# haasoscope_pro_fpga_board_-_power_and_fa.net
KiCad netlist of a schematic drawn in EAGLE
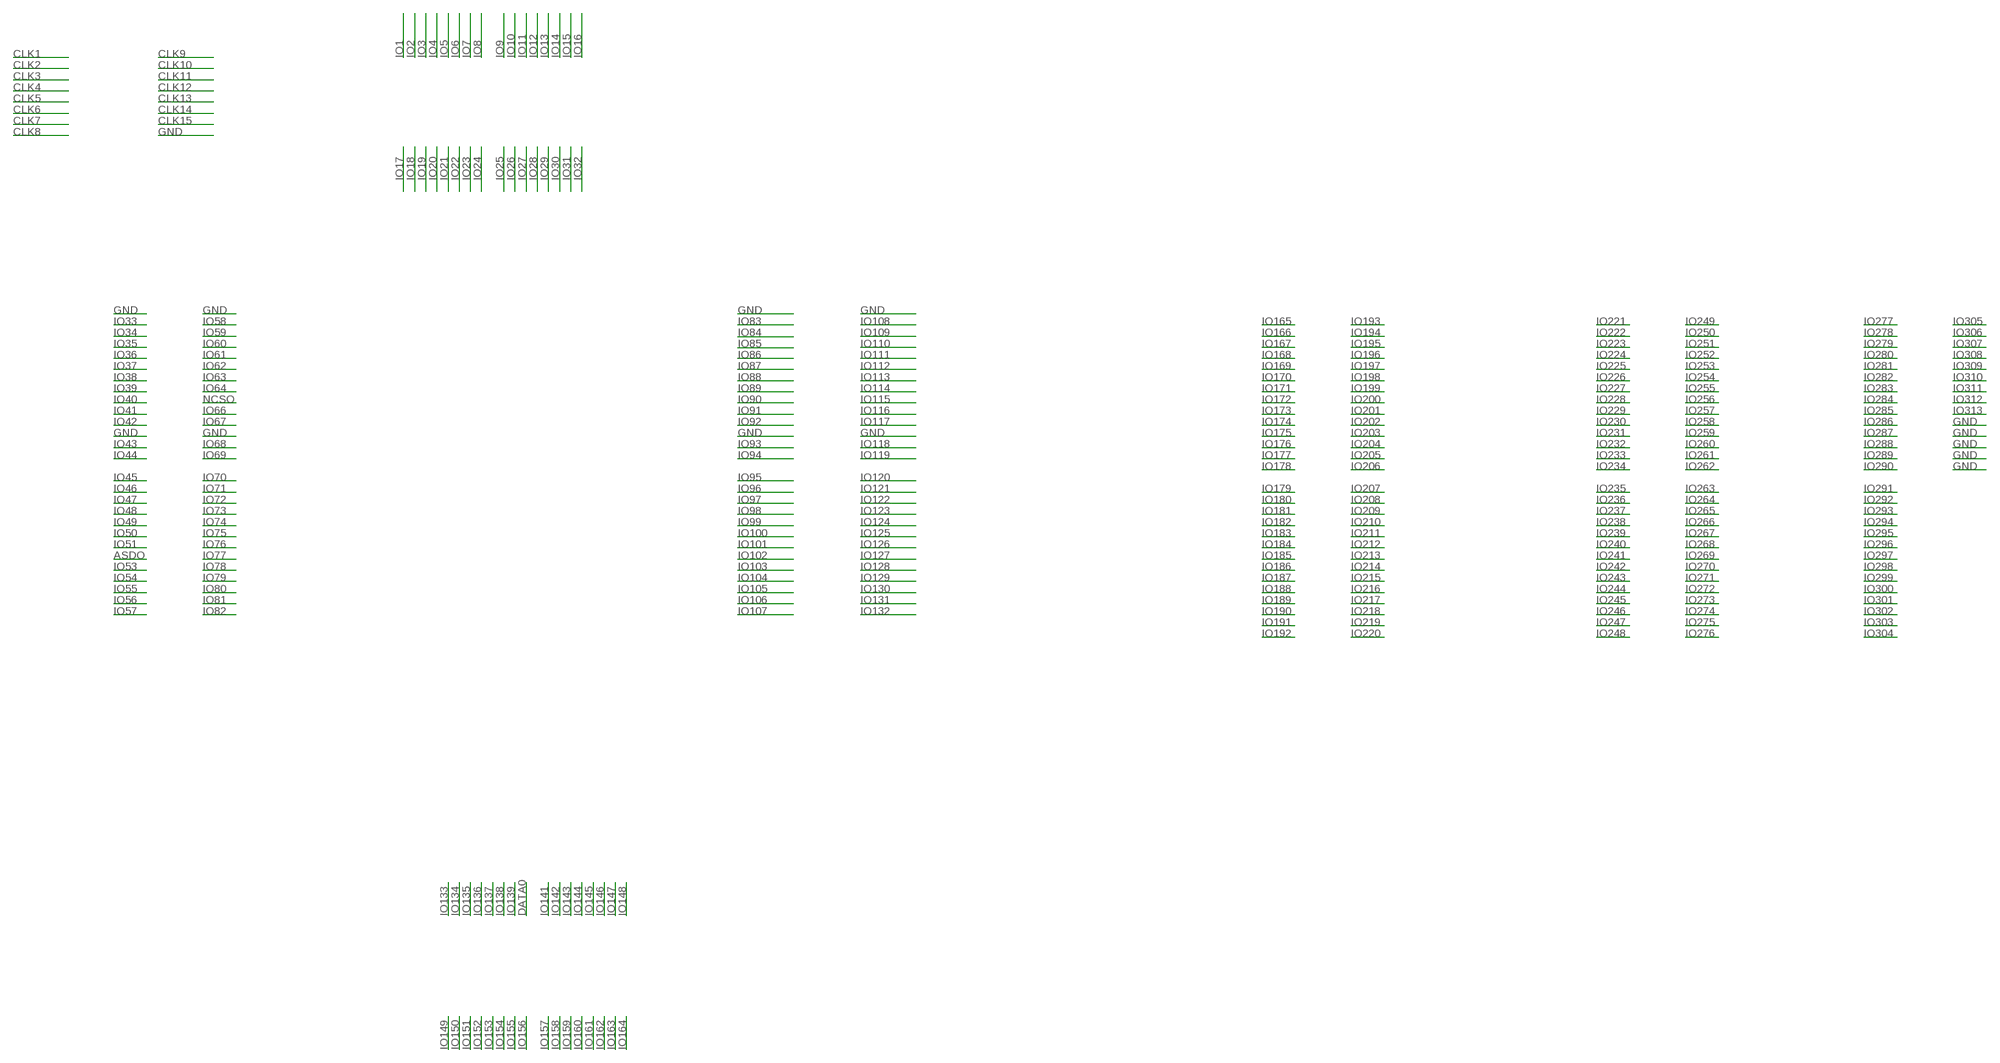
[diagram p0: schematic, sheet 1]
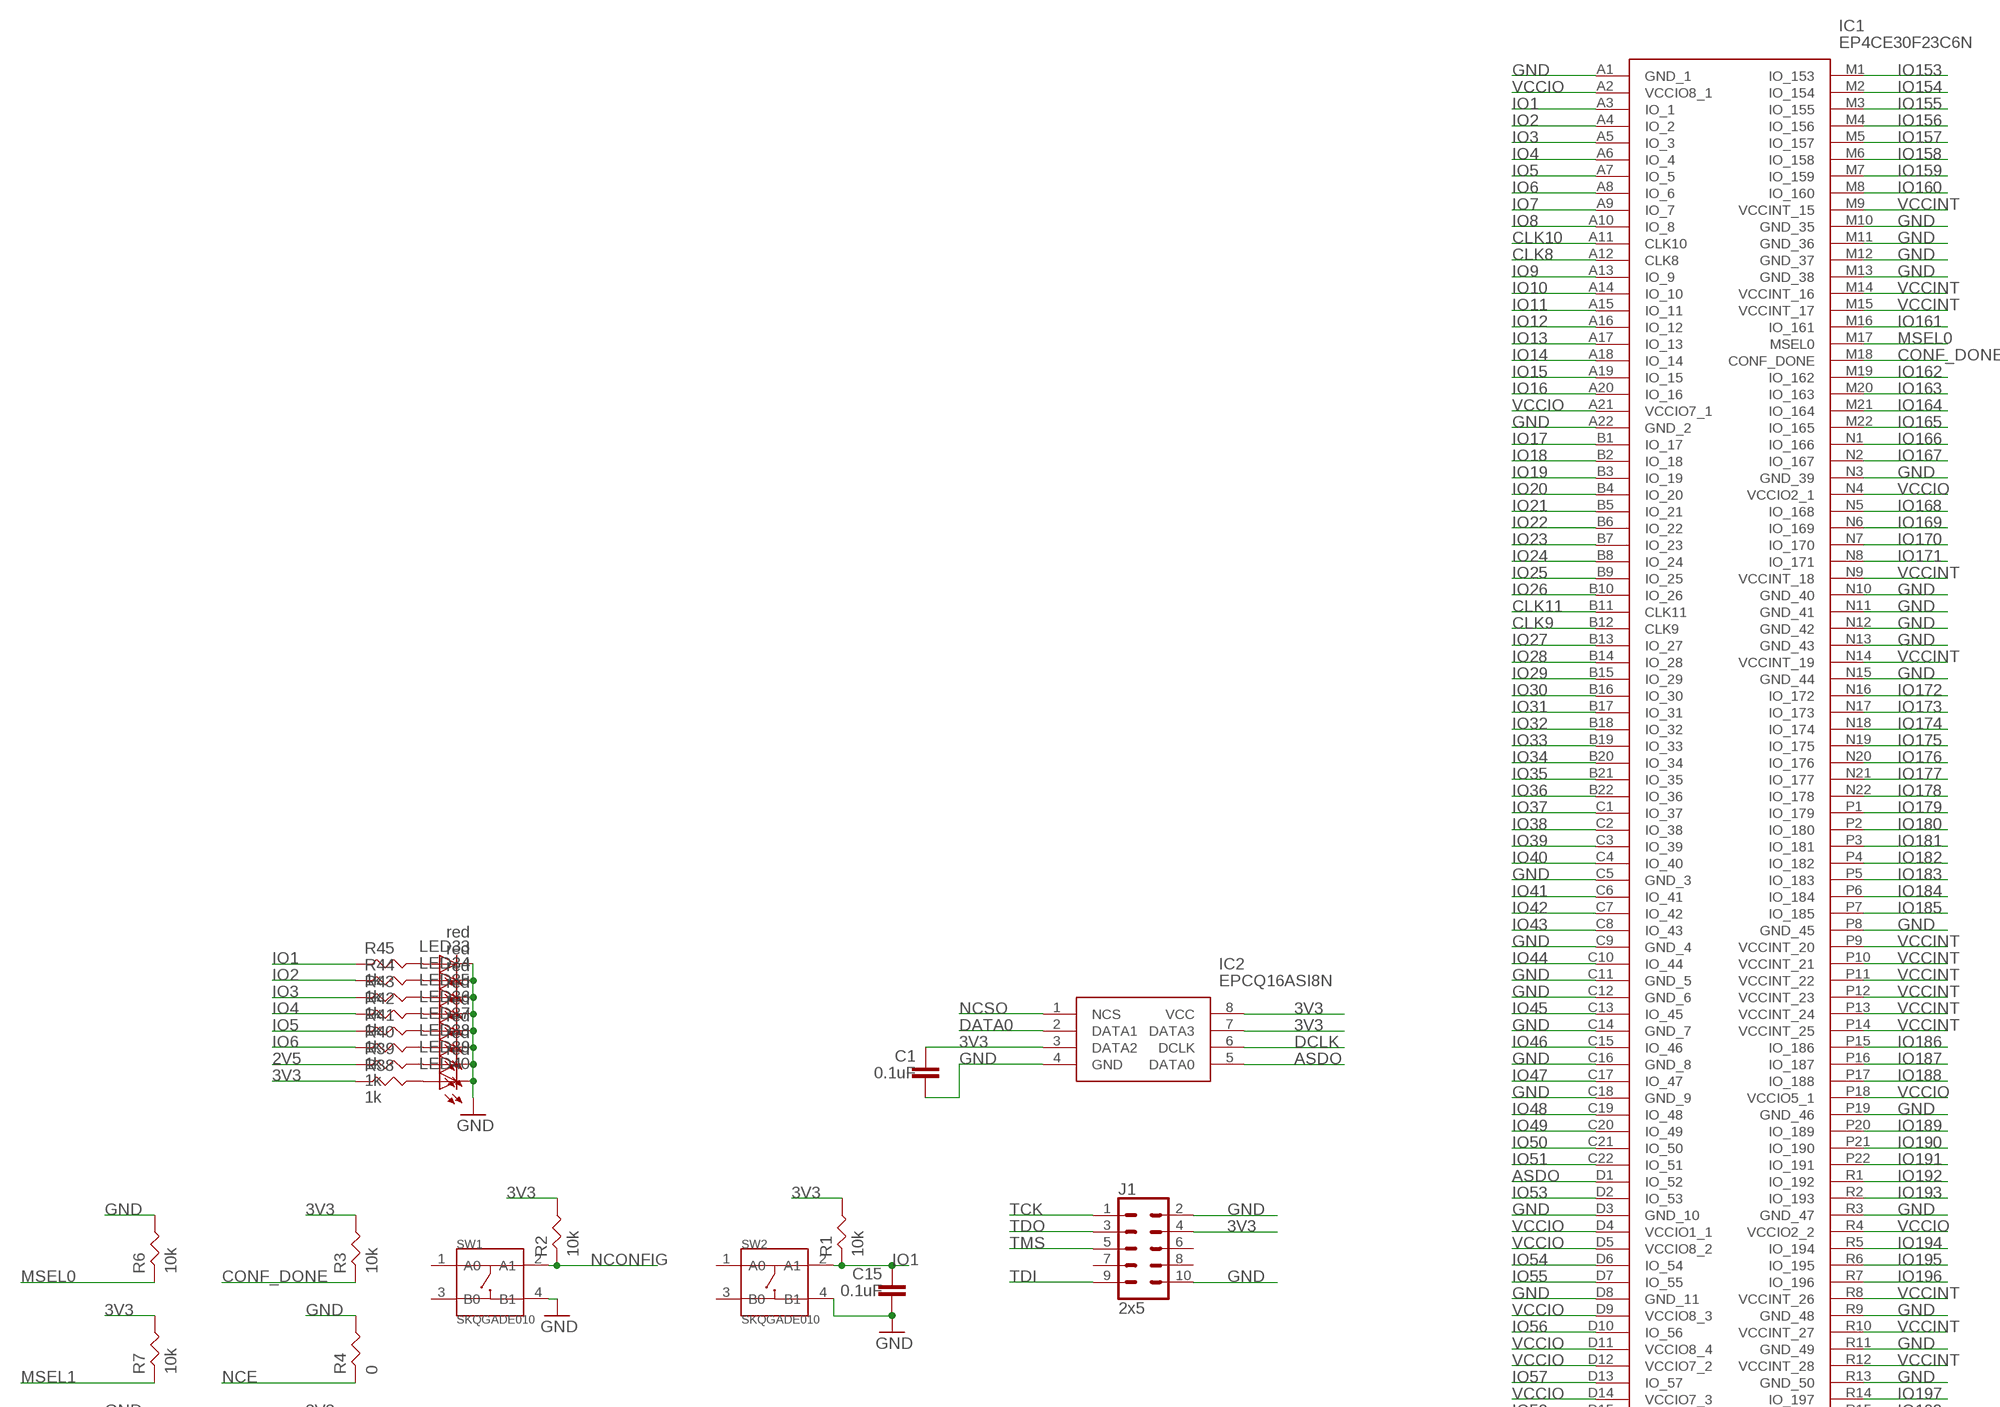
[diagram p1: schematic, sheet 2, part 1 of 2]
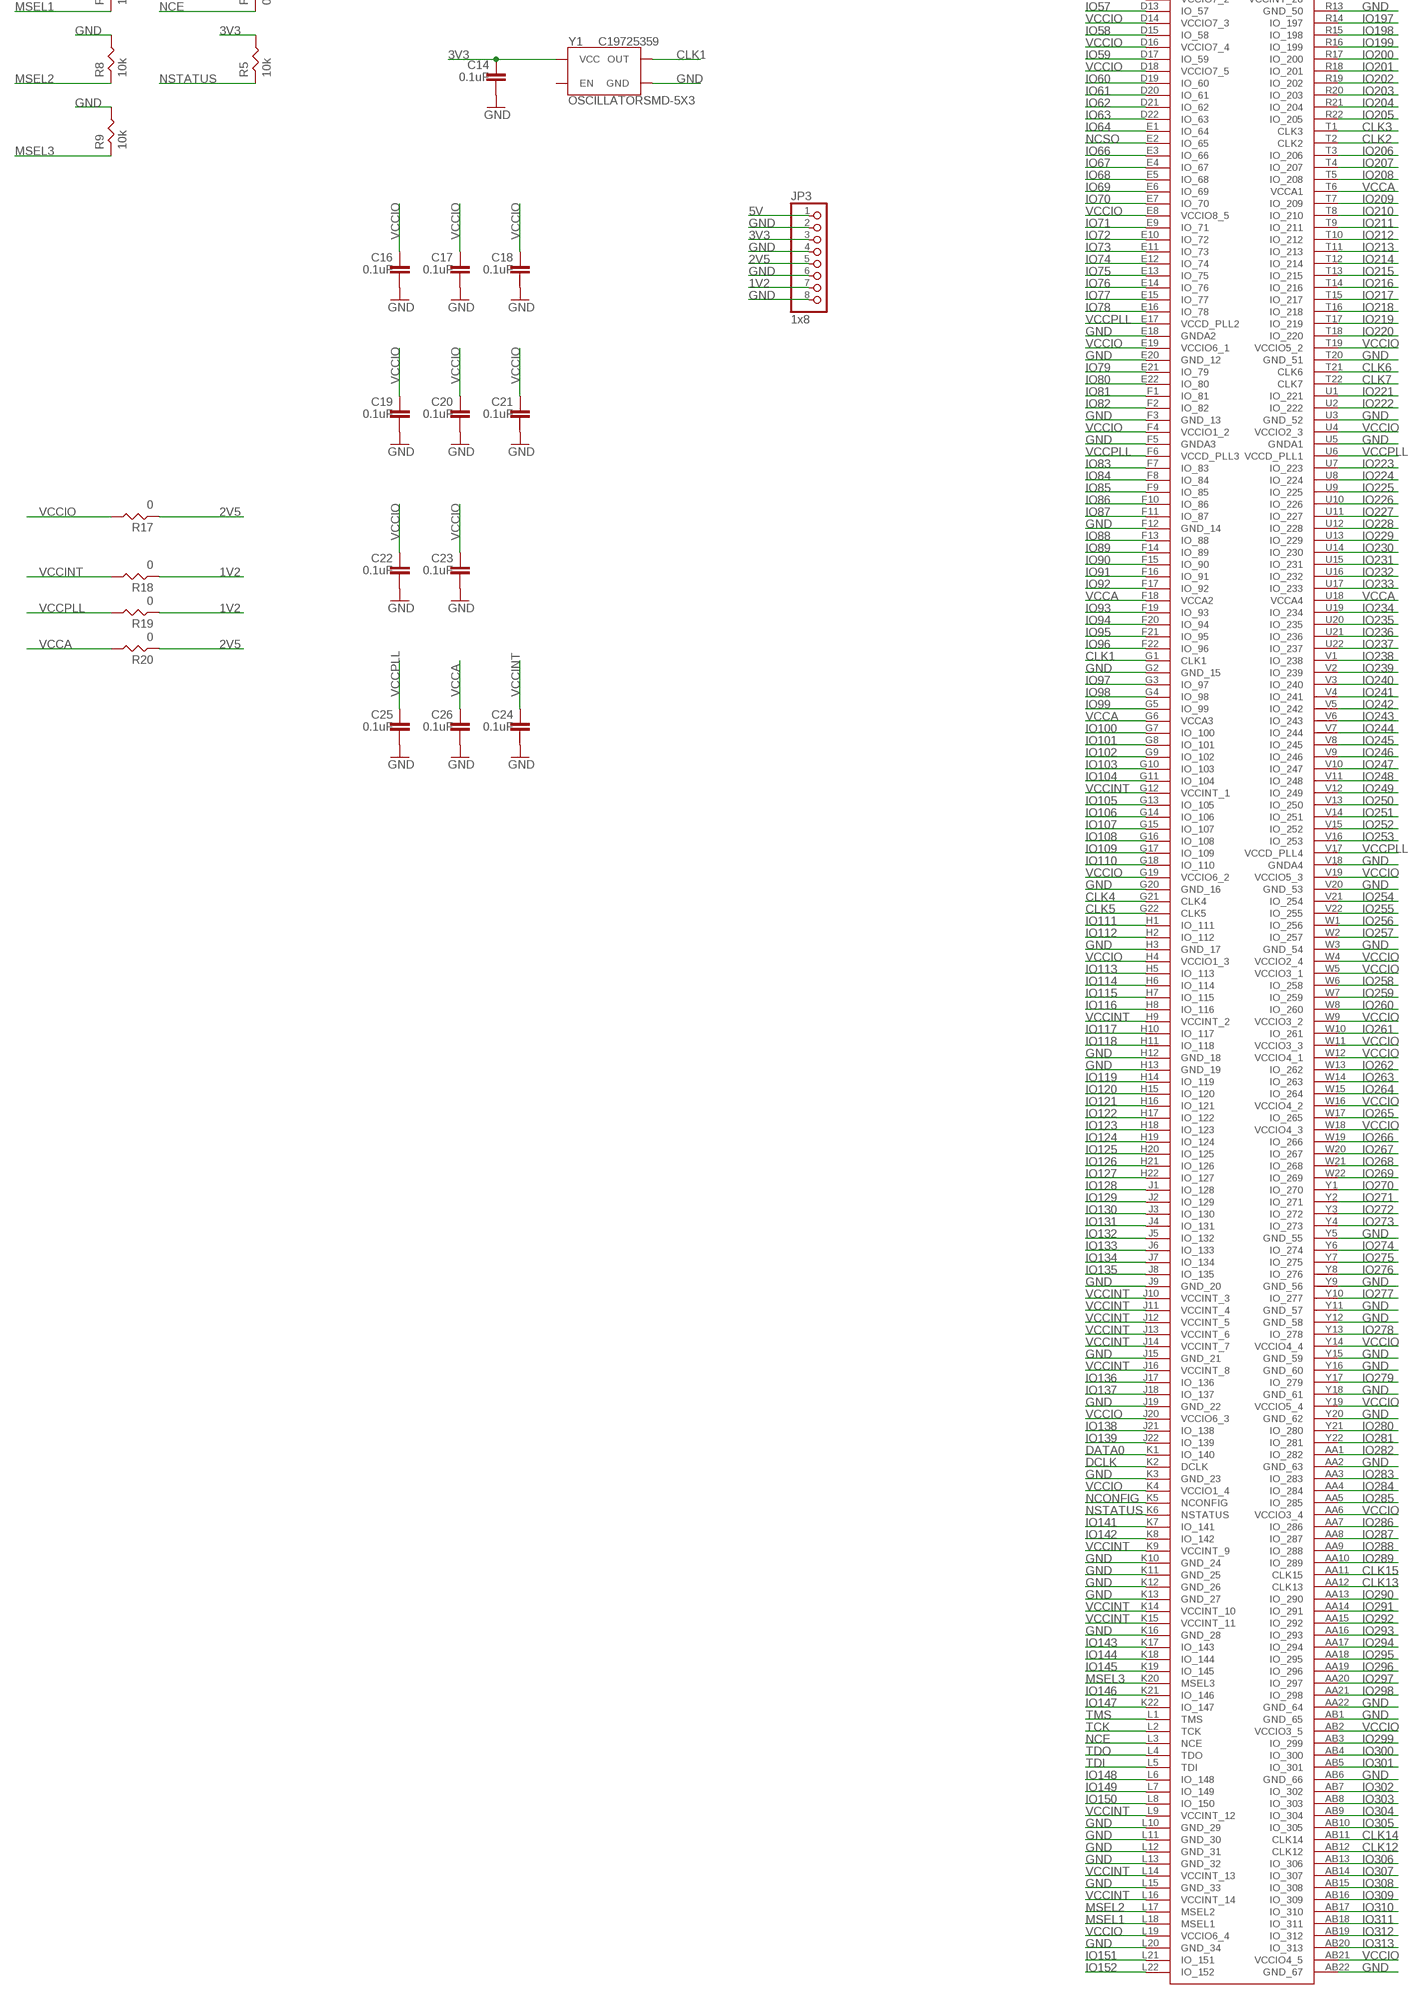
[diagram p2: schematic, sheet 2, part 2 of 2]
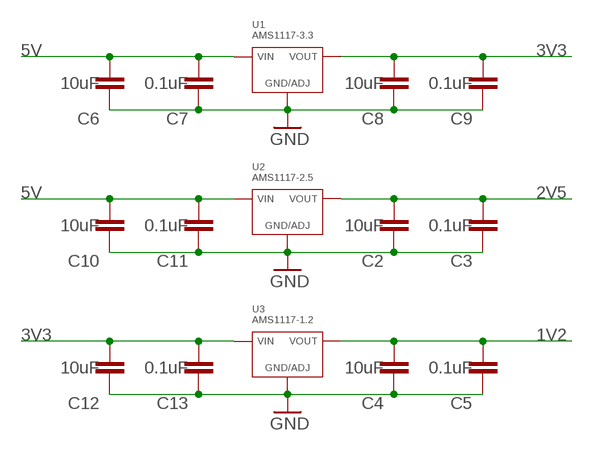
[diagram p3: schematic, sheet 3]

(export (version "E")
  (design (tool "Eeschema 10.0.6"))
  (components
    (comp (ref "C2")
      (value "10uF")
      (footprint "eagle-import:RESC0805_N")
      (libsource (lib "eagle-import") (part "CAPACITOR_0805_N"))
    )
    (comp (ref "C3")
      (value "0.1uF")
      (footprint "eagle-import:RESC0402_N")
      (libsource (lib "eagle-import") (part "CAPACITOR_0402_N"))
    )
    (comp (ref "C4")
      (value "10uF")
      (footprint "eagle-import:RESC0805_N")
      (libsource (lib "eagle-import") (part "CAPACITOR_0805_N"))
    )
    (comp (ref "C5")
      (value "0.1uF")
      (footprint "eagle-import:RESC0402_N")
      (libsource (lib "eagle-import") (part "CAPACITOR_0402_N"))
    )
    (comp (ref "C6")
      (value "10uF")
      (footprint "eagle-import:RESC0805_N")
      (libsource (lib "eagle-import") (part "CAPACITOR_0805_N"))
    )
    (comp (ref "C7")
      (value "0.1uF")
      (footprint "eagle-import:RESC0402_N")
      (libsource (lib "eagle-import") (part "CAPACITOR_0402_N"))
    )
    (comp (ref "C8")
      (value "10uF")
      (footprint "eagle-import:RESC0805_N")
      (libsource (lib "eagle-import") (part "CAPACITOR_0805_N"))
    )
    (comp (ref "C9")
      (value "0.1uF")
      (footprint "eagle-import:RESC0402_N")
      (libsource (lib "eagle-import") (part "CAPACITOR_0402_N"))
    )
    (comp (ref "C10")
      (value "10uF")
      (footprint "eagle-import:RESC0805_N")
      (libsource (lib "eagle-import") (part "CAPACITOR_0805_N"))
    )
    (comp (ref "C11")
      (value "0.1uF")
      (footprint "eagle-import:RESC0402_N")
      (libsource (lib "eagle-import") (part "CAPACITOR_0402_N"))
    )
    (comp (ref "C12")
      (value "10uF")
      (footprint "eagle-import:RESC0805_N")
      (libsource (lib "eagle-import") (part "CAPACITOR_0805_N"))
    )
    (comp (ref "C13")
      (value "0.1uF")
      (footprint "eagle-import:RESC0402_N")
      (libsource (lib "eagle-import") (part "CAPACITOR_0402_N"))
    )
    (comp (ref "U1")
      (value "AMS1117-3.3")
      (footprint "eagle-import:SOT-223-3")
      (fields
        (field (name "HOUSEPART") "NO")
        (field (name "MPN") "NCP1117LPST33T3G")
        (field (name "MPN_1") "AMS1117-3.3")
      )
      (libsource (lib "eagle-import") (part "NCP1117LPST33T3G"))
    )
    (comp (ref "U2")
      (value "AMS1117-2.5")
      (footprint "eagle-import:SOT-223-3")
      (fields
        (field (name "HOUSEPART") "NO")
        (field (name "MPN") "NCP1117LPST33T3G")
        (field (name "MPN_1") "AMS1117-2.5")
      )
      (libsource (lib "eagle-import") (part "NCP1117LPST33T3G"))
    )
    (comp (ref "U3")
      (value "AMS1117-1.2")
      (footprint "eagle-import:SOT-223-3")
      (fields
        (field (name "HOUSEPART") "NO")
        (field (name "MPN") "NCP1117LPST33T3G")
        (field (name "MPN_1") "AMS1117-1.2")
      )
      (libsource (lib "eagle-import") (part "NCP1117LPST33T3G"))
    )
    (comp (ref "C1")
      (value "0.1uF")
      (footprint "eagle-import:RESC0402_N")
      (libsource (lib "eagle-import") (part "CAPACITOR_0402_N"))
    )
    (comp (ref "C14")
      (value "0.1uF")
      (footprint "eagle-import:RESC0402_N")
      (libsource (lib "eagle-import") (part "CAPACITOR_0402_N"))
    )
    (comp (ref "C15")
      (value "0.1uF")
      (footprint "eagle-import:RESC0402_N")
      (libsource (lib "eagle-import") (part "CAPACITOR_0402_N"))
    )
    (comp (ref "C16")
      (value "0.1uF")
      (footprint "eagle-import:RESC0402_N")
      (libsource (lib "eagle-import") (part "CAPACITOR_0402_N"))
    )
    (comp (ref "C17")
      (value "0.1uF")
      (footprint "eagle-import:RESC0402_N")
      (libsource (lib "eagle-import") (part "CAPACITOR_0402_N"))
    )
    (comp (ref "C18")
      (value "0.1uF")
      (footprint "eagle-import:RESC0402_N")
      (libsource (lib "eagle-import") (part "CAPACITOR_0402_N"))
    )
    (comp (ref "C19")
      (value "0.1uF")
      (footprint "eagle-import:RESC0402_N")
      (libsource (lib "eagle-import") (part "CAPACITOR_0402_N"))
    )
    (comp (ref "C20")
      (value "0.1uF")
      (footprint "eagle-import:RESC0402_N")
      (libsource (lib "eagle-import") (part "CAPACITOR_0402_N"))
    )
    (comp (ref "C21")
      (value "0.1uF")
      (footprint "eagle-import:RESC0402_N")
      (libsource (lib "eagle-import") (part "CAPACITOR_0402_N"))
    )
    (comp (ref "C22")
      (value "0.1uF")
      (footprint "eagle-import:RESC0402_N")
      (libsource (lib "eagle-import") (part "CAPACITOR_0402_N"))
    )
    (comp (ref "C23")
      (value "0.1uF")
      (footprint "eagle-import:RESC0402_N")
      (libsource (lib "eagle-import") (part "CAPACITOR_0402_N"))
    )
    (comp (ref "C24")
      (value "0.1uF")
      (footprint "eagle-import:RESC0402_N")
      (libsource (lib "eagle-import") (part "CAPACITOR_0402_N"))
    )
    (comp (ref "C25")
      (value "0.1uF")
      (footprint "eagle-import:RESC0402_N")
      (libsource (lib "eagle-import") (part "CAPACITOR_0402_N"))
    )
    (comp (ref "C26")
      (value "0.1uF")
      (footprint "eagle-import:RESC0402_N")
      (libsource (lib "eagle-import") (part "CAPACITOR_0402_N"))
    )
    (comp (ref "IC1")
      (value "EP4CE30F23C6N")
      (footprint "eagle-import:BGA484C100P22X22_2300X2300X240")
      (fields (field (name "MOUSER_PART_NUMBER") "989-EP4CE30F23C6N"))
      (libsource (lib "eagle-import") (part "EP4CE30F23C6N"))
    )
    (comp (ref "IC2")
      (value "EPCQ16ASI8N")
      (footprint "eagle-import:SOIC127P600X175-8N")
      (fields (field (name "MOUSER_PART_NUMBER") "989-EPCQ16ASI8N"))
      (libsource (lib "eagle-import") (part "EPCQ16ASI8N"))
    )
    (comp (ref "J1")
      (value "2x5")
      (footprint "eagle-import:2X5-SHROUDED")
      (libsource (lib "eagle-import") (part "CONN_05X2SHD"))
    )
    (comp (ref "JP3")
      (value "1x8")
      (footprint "eagle-import:1X08")
      (libsource (lib "eagle-import") (part "PINHD-1X8"))
    )
    (comp (ref "LED33")
      (value "red")
      (footprint "eagle-import:CHIP-LED0603")
      (libsource (lib "eagle-import") (part "LEDCHIP-LED0603"))
    )
    (comp (ref "LED34")
      (value "red")
      (footprint "eagle-import:CHIP-LED0603")
      (libsource (lib "eagle-import") (part "LEDCHIP-LED0603"))
    )
    (comp (ref "LED35")
      (value "red")
      (footprint "eagle-import:CHIP-LED0603")
      (libsource (lib "eagle-import") (part "LEDCHIP-LED0603"))
    )
    (comp (ref "LED36")
      (value "red")
      (footprint "eagle-import:CHIP-LED0603")
      (libsource (lib "eagle-import") (part "LEDCHIP-LED0603"))
    )
    (comp (ref "LED37")
      (value "red")
      (footprint "eagle-import:CHIP-LED0603")
      (libsource (lib "eagle-import") (part "LEDCHIP-LED0603"))
    )
    (comp (ref "LED38")
      (value "red")
      (footprint "eagle-import:CHIP-LED0603")
      (libsource (lib "eagle-import") (part "LEDCHIP-LED0603"))
    )
    (comp (ref "LED39")
      (value "red")
      (footprint "eagle-import:CHIP-LED0603")
      (libsource (lib "eagle-import") (part "LEDCHIP-LED0603"))
    )
    (comp (ref "LED40")
      (value "red")
      (footprint "eagle-import:CHIP-LED0603")
      (libsource (lib "eagle-import") (part "LEDCHIP-LED0603"))
    )
    (comp (ref "R1")
      (value "10k")
      (footprint "eagle-import:RES-0402")
      (libsource (lib "eagle-import") (part "RES-0402"))
    )
    (comp (ref "R2")
      (value "10k")
      (footprint "eagle-import:RES-0402")
      (libsource (lib "eagle-import") (part "RES-0402"))
    )
    (comp (ref "R3")
      (value "10k")
      (footprint "eagle-import:RES-0402")
      (libsource (lib "eagle-import") (part "RES-0402"))
    )
    (comp (ref "R4")
      (value "0")
      (footprint "eagle-import:RES-0402")
      (libsource (lib "eagle-import") (part "RES-0402"))
    )
    (comp (ref "R5")
      (value "10k")
      (footprint "eagle-import:RES-0402")
      (libsource (lib "eagle-import") (part "RES-0402"))
    )
    (comp (ref "R6")
      (value "10k")
      (footprint "eagle-import:RES-0402")
      (libsource (lib "eagle-import") (part "RES-0402"))
    )
    (comp (ref "R7")
      (value "10k")
      (footprint "eagle-import:RES-0402")
      (libsource (lib "eagle-import") (part "RES-0402"))
    )
    (comp (ref "R8")
      (value "10k")
      (footprint "eagle-import:RES-0402")
      (libsource (lib "eagle-import") (part "RES-0402"))
    )
    (comp (ref "R9")
      (value "10k")
      (footprint "eagle-import:RES-0402")
      (libsource (lib "eagle-import") (part "RES-0402"))
    )
    (comp (ref "R17")
      (value "0")
      (footprint "eagle-import:RES-0402")
      (libsource (lib "eagle-import") (part "RES-0402"))
    )
    (comp (ref "R18")
      (value "0")
      (footprint "eagle-import:RES-0402")
      (libsource (lib "eagle-import") (part "RES-0402"))
    )
    (comp (ref "R19")
      (value "0")
      (footprint "eagle-import:RES-0402")
      (libsource (lib "eagle-import") (part "RES-0402"))
    )
    (comp (ref "R20")
      (value "0")
      (footprint "eagle-import:RES-0402")
      (libsource (lib "eagle-import") (part "RES-0402"))
    )
    (comp (ref "R38")
      (value "1k")
      (footprint "eagle-import:RES-0402")
      (libsource (lib "eagle-import") (part "RES-0402"))
    )
    (comp (ref "R39")
      (value "1k")
      (footprint "eagle-import:RES-0402")
      (libsource (lib "eagle-import") (part "RES-0402"))
    )
    (comp (ref "R40")
      (value "1k")
      (footprint "eagle-import:RES-0402")
      (libsource (lib "eagle-import") (part "RES-0402"))
    )
    (comp (ref "R41")
      (value "1k")
      (footprint "eagle-import:RES-0402")
      (libsource (lib "eagle-import") (part "RES-0402"))
    )
    (comp (ref "R42")
      (value "1k")
      (footprint "eagle-import:RES-0402")
      (libsource (lib "eagle-import") (part "RES-0402"))
    )
    (comp (ref "R43")
      (value "1k")
      (footprint "eagle-import:RES-0402")
      (libsource (lib "eagle-import") (part "RES-0402"))
    )
    (comp (ref "R44")
      (value "1k")
      (footprint "eagle-import:RES-0402")
      (libsource (lib "eagle-import") (part "RES-0402"))
    )
    (comp (ref "R45")
      (value "1k")
      (footprint "eagle-import:RES-0402")
      (libsource (lib "eagle-import") (part "RES-0402"))
    )
    (comp (ref "SW1")
      (value "SKQGADE010")
      (footprint "eagle-import:SW4-SMD-5.2X5.2X1.5MM")
      (libsource (lib "eagle-import") (part "SMD-BUTTON(4P-5.2X5.2X1.5MM-SKQGADE010)-SKQGADE010"))
    )
    (comp (ref "SW2")
      (value "SKQGADE010")
      (footprint "eagle-import:SW4-SMD-5.2X5.2X1.5MM")
      (libsource (lib "eagle-import") (part "SMD-BUTTON(4P-5.2X5.2X1.5MM-SKQGADE010)-SKQGADE010"))
    )
    (comp (ref "Y1")
      (value "OSCILLATORSMD-5X3")
      (footprint "eagle-import:OSCILLATOR-SMD-5X3.2")
      (fields (field (name "LCSC") "C19725359"))
      (libsource (lib "eagle-import") (part "OSCILLATORSMD-5X3"))
    )
  )
  (nets
    (net (code "1") (name "1V2") (class "Default")
      (node (ref "C4") (pin "2") (pinfunction "2_2") (pintype "passive"))
      (node (ref "C5") (pin "2") (pinfunction "2_2") (pintype "passive"))
      (node (ref "JP3") (pin "7") (pinfunction "7_7") (pintype "passive"))
      (node (ref "R18") (pin "P$1") (pinfunction "P$1_P$1") (pintype "bidirectional"))
      (node (ref "R19") (pin "P$1") (pinfunction "P$1_P$1") (pintype "bidirectional"))
      (node (ref "U3") (pin "P$1") (pinfunction "VOUT_P$1") (pintype "bidirectional"))
      (node (ref "U3") (pin "P$3") (pinfunction "VOUT_P$3") (pintype "bidirectional"))
    )
    (net (code "2") (name "2V5") (class "Default")
      (node (ref "C2") (pin "2") (pinfunction "2_2") (pintype "passive"))
      (node (ref "C3") (pin "2") (pinfunction "2_2") (pintype "passive"))
      (node (ref "JP3") (pin "5") (pinfunction "5_5") (pintype "passive"))
      (node (ref "R17") (pin "P$1") (pinfunction "P$1_P$1") (pintype "bidirectional"))
      (node (ref "R20") (pin "P$1") (pinfunction "P$1_P$1") (pintype "bidirectional"))
      (node (ref "R39") (pin "P$1") (pinfunction "P$1_P$1") (pintype "bidirectional"))
      (node (ref "U2") (pin "P$1") (pinfunction "VOUT_P$1") (pintype "bidirectional"))
      (node (ref "U2") (pin "P$3") (pinfunction "VOUT_P$3") (pintype "bidirectional"))
    )
    (net (code "3") (name "3V3") (class "Default")
      (node (ref "C1") (pin "2") (pinfunction "2_2") (pintype "passive"))
      (node (ref "C12") (pin "2") (pinfunction "2_2") (pintype "passive"))
      (node (ref "C13") (pin "2") (pinfunction "2_2") (pintype "passive"))
      (node (ref "C14") (pin "2") (pinfunction "2_2") (pintype "passive"))
      (node (ref "C8") (pin "2") (pinfunction "2_2") (pintype "passive"))
      (node (ref "C9") (pin "2") (pinfunction "2_2") (pintype "passive"))
      (node (ref "IC2") (pin "3") (pinfunction "DATA2_3") (pintype "bidirectional"))
      (node (ref "IC2") (pin "7") (pinfunction "DATA3_7") (pintype "bidirectional"))
      (node (ref "IC2") (pin "8") (pinfunction "VCC_8") (pintype "bidirectional"))
      (node (ref "J1") (pin "4") (pinfunction "4_4") (pintype "passive"))
      (node (ref "JP3") (pin "3") (pinfunction "3_3") (pintype "passive"))
      (node (ref "R1") (pin "P$2") (pinfunction "P$2_P$2") (pintype "bidirectional"))
      (node (ref "R2") (pin "P$2") (pinfunction "P$2_P$2") (pintype "bidirectional"))
      (node (ref "R3") (pin "P$2") (pinfunction "P$2_P$2") (pintype "bidirectional"))
      (node (ref "R38") (pin "P$1") (pinfunction "P$1_P$1") (pintype "bidirectional"))
      (node (ref "R5") (pin "P$2") (pinfunction "P$2_P$2") (pintype "bidirectional"))
      (node (ref "R7") (pin "P$2") (pinfunction "P$2_P$2") (pintype "bidirectional"))
      (node (ref "U1") (pin "P$1") (pinfunction "VOUT_P$1") (pintype "bidirectional"))
      (node (ref "U1") (pin "P$3") (pinfunction "VOUT_P$3") (pintype "bidirectional"))
      (node (ref "U3") (pin "P$4") (pinfunction "VIN_P$4") (pintype "bidirectional"))
      (node (ref "Y1") (pin "4") (pinfunction "VCC_4") (pintype "bidirectional"))
    )
    (net (code "4") (name "5V") (class "Default")
      (node (ref "C10") (pin "2") (pinfunction "2_2") (pintype "passive"))
      (node (ref "C11") (pin "2") (pinfunction "2_2") (pintype "passive"))
      (node (ref "C6") (pin "2") (pinfunction "2_2") (pintype "passive"))
      (node (ref "C7") (pin "2") (pinfunction "2_2") (pintype "passive"))
      (node (ref "JP3") (pin "1") (pinfunction "1_1") (pintype "passive"))
      (node (ref "U1") (pin "P$4") (pinfunction "VIN_P$4") (pintype "bidirectional"))
      (node (ref "U2") (pin "P$4") (pinfunction "VIN_P$4") (pintype "bidirectional"))
    )
    (net (code "5") (name "ASDO") (class "Default")
      (node (ref "IC1") (pin "D1") (pinfunction "IO_52_D1") (pintype "bidirectional"))
      (node (ref "IC2") (pin "5") (pinfunction "DATA0_5") (pintype "bidirectional"))
    )
    (net (code "6") (name "CLK1") (class "Default")
      (node (ref "IC1") (pin "G1") (pinfunction "CLK1_G1") (pintype "bidirectional"))
      (node (ref "Y1") (pin "3") (pinfunction "OUT_3") (pintype "bidirectional"))
    )
    (net (code "7") (name "CLK2") (class "Default")
      (node (ref "IC1") (pin "T2") (pinfunction "CLK2_T2") (pintype "bidirectional"))
    )
    (net (code "8") (name "CLK3") (class "Default")
      (node (ref "IC1") (pin "T1") (pinfunction "CLK3_T1") (pintype "bidirectional"))
    )
    (net (code "9") (name "CLK4") (class "Default")
      (node (ref "IC1") (pin "G21") (pinfunction "CLK4_G21") (pintype "bidirectional"))
    )
    (net (code "10") (name "CLK5") (class "Default")
      (node (ref "IC1") (pin "G22") (pinfunction "CLK5_G22") (pintype "bidirectional"))
    )
    (net (code "11") (name "CLK6") (class "Default")
      (node (ref "IC1") (pin "T21") (pinfunction "CLK6_T21") (pintype "bidirectional"))
    )
    (net (code "12") (name "CLK7") (class "Default")
      (node (ref "IC1") (pin "T22") (pinfunction "CLK7_T22") (pintype "bidirectional"))
    )
    (net (code "13") (name "CLK8") (class "Default")
      (node (ref "IC1") (pin "A12") (pinfunction "CLK8_A12") (pintype "bidirectional"))
    )
    (net (code "14") (name "CLK9") (class "Default")
      (node (ref "IC1") (pin "B12") (pinfunction "CLK9_B12") (pintype "bidirectional"))
    )
    (net (code "15") (name "CLK10") (class "Default")
      (node (ref "IC1") (pin "A11") (pinfunction "CLK10_A11") (pintype "bidirectional"))
    )
    (net (code "16") (name "CLK11") (class "Default")
      (node (ref "IC1") (pin "B11") (pinfunction "CLK11_B11") (pintype "bidirectional"))
    )
    (net (code "17") (name "CLK12") (class "Default")
      (node (ref "IC1") (pin "AB12") (pinfunction "CLK12_AB12") (pintype "bidirectional"))
    )
    (net (code "18") (name "CLK13") (class "Default")
      (node (ref "IC1") (pin "AA12") (pinfunction "CLK13_AA12") (pintype "bidirectional"))
    )
    (net (code "19") (name "CLK14") (class "Default")
      (node (ref "IC1") (pin "AB11") (pinfunction "CLK14_AB11") (pintype "bidirectional"))
    )
    (net (code "20") (name "CLK15") (class "Default")
      (node (ref "IC1") (pin "AA11") (pinfunction "CLK15_AA11") (pintype "bidirectional"))
    )
    (net (code "21") (name "CONF_DONE") (class "Default")
      (node (ref "IC1") (pin "M18") (pinfunction "CONF_DONE_M18") (pintype "bidirectional"))
      (node (ref "R3") (pin "P$1") (pinfunction "P$1_P$1") (pintype "bidirectional"))
    )
    (net (code "22") (name "DATA0") (class "Default")
      (node (ref "IC1") (pin "K1") (pinfunction "IO_140_K1") (pintype "bidirectional"))
      (node (ref "IC2") (pin "2") (pinfunction "DATA1_2") (pintype "bidirectional"))
    )
    (net (code "23") (name "DCLK") (class "Default")
      (node (ref "IC1") (pin "K2") (pinfunction "DCLK_K2") (pintype "bidirectional"))
      (node (ref "IC2") (pin "6") (pinfunction "DCLK_6") (pintype "bidirectional"))
    )
    (net (code "24") (name "GND") (class "Default")
      (node (ref "C1") (pin "1") (pinfunction "1_1") (pintype "passive"))
      (node (ref "C10") (pin "1") (pinfunction "1_1") (pintype "passive"))
      (node (ref "C11") (pin "1") (pinfunction "1_1") (pintype "passive"))
      (node (ref "C12") (pin "1") (pinfunction "1_1") (pintype "passive"))
      (node (ref "C13") (pin "1") (pinfunction "1_1") (pintype "passive"))
      (node (ref "C14") (pin "1") (pinfunction "1_1") (pintype "passive"))
      (node (ref "C15") (pin "1") (pinfunction "1_1") (pintype "passive"))
      (node (ref "C16") (pin "1") (pinfunction "1_1") (pintype "passive"))
      (node (ref "C17") (pin "1") (pinfunction "1_1") (pintype "passive"))
      (node (ref "C18") (pin "1") (pinfunction "1_1") (pintype "passive"))
      (node (ref "C19") (pin "1") (pinfunction "1_1") (pintype "passive"))
      (node (ref "C2") (pin "1") (pinfunction "1_1") (pintype "passive"))
      (node (ref "C20") (pin "1") (pinfunction "1_1") (pintype "passive"))
      (node (ref "C21") (pin "1") (pinfunction "1_1") (pintype "passive"))
      (node (ref "C22") (pin "1") (pinfunction "1_1") (pintype "passive"))
      (node (ref "C23") (pin "1") (pinfunction "1_1") (pintype "passive"))
      (node (ref "C24") (pin "1") (pinfunction "1_1") (pintype "passive"))
      (node (ref "C25") (pin "1") (pinfunction "1_1") (pintype "passive"))
      (node (ref "C26") (pin "1") (pinfunction "1_1") (pintype "passive"))
      (node (ref "C3") (pin "1") (pinfunction "1_1") (pintype "passive"))
      (node (ref "C4") (pin "1") (pinfunction "1_1") (pintype "passive"))
      (node (ref "C5") (pin "1") (pinfunction "1_1") (pintype "passive"))
      (node (ref "C6") (pin "1") (pinfunction "1_1") (pintype "passive"))
      (node (ref "C7") (pin "1") (pinfunction "1_1") (pintype "passive"))
      (node (ref "C8") (pin "1") (pinfunction "1_1") (pintype "passive"))
      (node (ref "C9") (pin "1") (pinfunction "1_1") (pintype "passive"))
      (node (ref "IC1") (pin "A1") (pinfunction "GND_1_A1") (pintype "bidirectional"))
      (node (ref "IC1") (pin "A22") (pinfunction "GND_2_A22") (pintype "bidirectional"))
      (node (ref "IC1") (pin "AA2") (pinfunction "GND_63_AA2") (pintype "bidirectional"))
      (node (ref "IC1") (pin "AA22") (pinfunction "GND_64_AA22") (pintype "bidirectional"))
      (node (ref "IC1") (pin "AB1") (pinfunction "GND_65_AB1") (pintype "bidirectional"))
      (node (ref "IC1") (pin "AB22") (pinfunction "GND_67_AB22") (pintype "bidirectional"))
      (node (ref "IC1") (pin "AB6") (pinfunction "GND_66_AB6") (pintype "bidirectional"))
      (node (ref "IC1") (pin "C11") (pinfunction "GND_5_C11") (pintype "bidirectional"))
      (node (ref "IC1") (pin "C12") (pinfunction "GND_6_C12") (pintype "bidirectional"))
      (node (ref "IC1") (pin "C14") (pinfunction "GND_7_C14") (pintype "bidirectional"))
      (node (ref "IC1") (pin "C16") (pinfunction "GND_8_C16") (pintype "bidirectional"))
      (node (ref "IC1") (pin "C18") (pinfunction "GND_9_C18") (pintype "bidirectional"))
      (node (ref "IC1") (pin "C5") (pinfunction "GND_3_C5") (pintype "bidirectional"))
      (node (ref "IC1") (pin "C9") (pinfunction "GND_4_C9") (pintype "bidirectional"))
      (node (ref "IC1") (pin "D3") (pinfunction "GND_10_D3") (pintype "bidirectional"))
      (node (ref "IC1") (pin "D8") (pinfunction "GND_11_D8") (pintype "bidirectional"))
      (node (ref "IC1") (pin "E18") (pinfunction "GNDA2_E18") (pintype "bidirectional"))
      (node (ref "IC1") (pin "E20") (pinfunction "GND_12_E20") (pintype "bidirectional"))
      (node (ref "IC1") (pin "F12") (pinfunction "GND_14_F12") (pintype "bidirectional"))
      (node (ref "IC1") (pin "F3") (pinfunction "GND_13_F3") (pintype "bidirectional"))
      (node (ref "IC1") (pin "F5") (pinfunction "GNDA3_F5") (pintype "bidirectional"))
      (node (ref "IC1") (pin "G2") (pinfunction "GND_15_G2") (pintype "bidirectional"))
      (node (ref "IC1") (pin "G20") (pinfunction "GND_16_G20") (pintype "bidirectional"))
      (node (ref "IC1") (pin "H12") (pinfunction "GND_18_H12") (pintype "bidirectional"))
      (node (ref "IC1") (pin "H13") (pinfunction "GND_19_H13") (pintype "bidirectional"))
      (node (ref "IC1") (pin "H3") (pinfunction "GND_17_H3") (pintype "bidirectional"))
      (node (ref "IC1") (pin "J15") (pinfunction "GND_21_J15") (pintype "bidirectional"))
      (node (ref "IC1") (pin "J19") (pinfunction "GND_22_J19") (pintype "bidirectional"))
      (node (ref "IC1") (pin "J9") (pinfunction "GND_20_J9") (pintype "bidirectional"))
      (node (ref "IC1") (pin "K10") (pinfunction "GND_24_K10") (pintype "bidirectional"))
      (node (ref "IC1") (pin "K11") (pinfunction "GND_25_K11") (pintype "bidirectional"))
      (node (ref "IC1") (pin "K12") (pinfunction "GND_26_K12") (pintype "bidirectional"))
      (node (ref "IC1") (pin "K13") (pinfunction "GND_27_K13") (pintype "bidirectional"))
      (node (ref "IC1") (pin "K16") (pinfunction "GND_28_K16") (pintype "bidirectional"))
      (node (ref "IC1") (pin "K3") (pinfunction "GND_23_K3") (pintype "bidirectional"))
      (node (ref "IC1") (pin "L10") (pinfunction "GND_29_L10") (pintype "bidirectional"))
      (node (ref "IC1") (pin "L11") (pinfunction "GND_30_L11") (pintype "bidirectional"))
      (node (ref "IC1") (pin "L12") (pinfunction "GND_31_L12") (pintype "bidirectional"))
      (node (ref "IC1") (pin "L13") (pinfunction "GND_32_L13") (pintype "bidirectional"))
      (node (ref "IC1") (pin "L15") (pinfunction "GND_33_L15") (pintype "bidirectional"))
      (node (ref "IC1") (pin "L20") (pinfunction "GND_34_L20") (pintype "bidirectional"))
      (node (ref "IC1") (pin "M10") (pinfunction "GND_35_M10") (pintype "bidirectional"))
      (node (ref "IC1") (pin "M11") (pinfunction "GND_36_M11") (pintype "bidirectional"))
      (node (ref "IC1") (pin "M12") (pinfunction "GND_37_M12") (pintype "bidirectional"))
      (node (ref "IC1") (pin "M13") (pinfunction "GND_38_M13") (pintype "bidirectional"))
      (node (ref "IC1") (pin "N10") (pinfunction "GND_40_N10") (pintype "bidirectional"))
      (node (ref "IC1") (pin "N11") (pinfunction "GND_41_N11") (pintype "bidirectional"))
      (node (ref "IC1") (pin "N12") (pinfunction "GND_42_N12") (pintype "bidirectional"))
      (node (ref "IC1") (pin "N13") (pinfunction "GND_43_N13") (pintype "bidirectional"))
      (node (ref "IC1") (pin "N15") (pinfunction "GND_44_N15") (pintype "bidirectional"))
      (node (ref "IC1") (pin "N3") (pinfunction "GND_39_N3") (pintype "bidirectional"))
      (node (ref "IC1") (pin "P19") (pinfunction "GND_46_P19") (pintype "bidirectional"))
      (node (ref "IC1") (pin "P8") (pinfunction "GND_45_P8") (pintype "bidirectional"))
      (node (ref "IC1") (pin "R11") (pinfunction "GND_49_R11") (pintype "bidirectional"))
      (node (ref "IC1") (pin "R13") (pinfunction "GND_50_R13") (pintype "bidirectional"))
      (node (ref "IC1") (pin "R3") (pinfunction "GND_47_R3") (pintype "bidirectional"))
      (node (ref "IC1") (pin "R9") (pinfunction "GND_48_R9") (pintype "bidirectional"))
      (node (ref "IC1") (pin "T20") (pinfunction "GND_51_T20") (pintype "bidirectional"))
      (node (ref "IC1") (pin "U3") (pinfunction "GND_52_U3") (pintype "bidirectional"))
      (node (ref "IC1") (pin "U5") (pinfunction "GNDA1_U5") (pintype "bidirectional"))
      (node (ref "IC1") (pin "V18") (pinfunction "GNDA4_V18") (pintype "bidirectional"))
      (node (ref "IC1") (pin "V20") (pinfunction "GND_53_V20") (pintype "bidirectional"))
      (node (ref "IC1") (pin "W3") (pinfunction "GND_54_W3") (pintype "bidirectional"))
      (node (ref "IC1") (pin "Y11") (pinfunction "GND_57_Y11") (pintype "bidirectional"))
      (node (ref "IC1") (pin "Y12") (pinfunction "GND_58_Y12") (pintype "bidirectional"))
      (node (ref "IC1") (pin "Y15") (pinfunction "GND_59_Y15") (pintype "bidirectional"))
      (node (ref "IC1") (pin "Y16") (pinfunction "GND_60_Y16") (pintype "bidirectional"))
      (node (ref "IC1") (pin "Y18") (pinfunction "GND_61_Y18") (pintype "bidirectional"))
      (node (ref "IC1") (pin "Y20") (pinfunction "GND_62_Y20") (pintype "bidirectional"))
      (node (ref "IC1") (pin "Y5") (pinfunction "GND_55_Y5") (pintype "bidirectional"))
      (node (ref "IC1") (pin "Y9") (pinfunction "GND_56_Y9") (pintype "bidirectional"))
      (node (ref "IC2") (pin "4") (pinfunction "GND_4") (pintype "bidirectional"))
      (node (ref "J1") (pin "10") (pinfunction "10_10") (pintype "passive"))
      (node (ref "J1") (pin "2") (pinfunction "2_2") (pintype "passive"))
      (node (ref "JP3") (pin "2") (pinfunction "2_2") (pintype "passive"))
      (node (ref "JP3") (pin "4") (pinfunction "4_4") (pintype "passive"))
      (node (ref "JP3") (pin "6") (pinfunction "6_6") (pintype "passive"))
      (node (ref "JP3") (pin "8") (pinfunction "8_8") (pintype "passive"))
      (node (ref "LED33") (pin "C") (pinfunction "C_C") (pintype "passive"))
      (node (ref "LED34") (pin "C") (pinfunction "C_C") (pintype "passive"))
      (node (ref "LED35") (pin "C") (pinfunction "C_C") (pintype "passive"))
      (node (ref "LED36") (pin "C") (pinfunction "C_C") (pintype "passive"))
      (node (ref "LED37") (pin "C") (pinfunction "C_C") (pintype "passive"))
      (node (ref "LED38") (pin "C") (pinfunction "C_C") (pintype "passive"))
      (node (ref "LED39") (pin "C") (pinfunction "C_C") (pintype "passive"))
      (node (ref "LED40") (pin "C") (pinfunction "C_C") (pintype "passive"))
      (node (ref "R4") (pin "P$2") (pinfunction "P$2_P$2") (pintype "bidirectional"))
      (node (ref "R6") (pin "P$2") (pinfunction "P$2_P$2") (pintype "bidirectional"))
      (node (ref "R8") (pin "P$2") (pinfunction "P$2_P$2") (pintype "bidirectional"))
      (node (ref "R9") (pin "P$2") (pinfunction "P$2_P$2") (pintype "bidirectional"))
      (node (ref "SW1") (pin "4") (pinfunction "B1_4") (pintype "bidirectional"))
      (node (ref "SW2") (pin "4") (pinfunction "B1_4") (pintype "bidirectional"))
      (node (ref "U1") (pin "P$2") (pinfunction "GND/ADJ_P$2") (pintype "bidirectional"))
      (node (ref "U2") (pin "P$2") (pinfunction "GND/ADJ_P$2") (pintype "bidirectional"))
      (node (ref "U3") (pin "P$2") (pinfunction "GND/ADJ_P$2") (pintype "bidirectional"))
      (node (ref "Y1") (pin "2") (pinfunction "GND_2") (pintype "bidirectional"))
    )
    (net (code "25") (name "IO1") (class "Default")
      (node (ref "C15") (pin "2") (pinfunction "2_2") (pintype "passive"))
      (node (ref "IC1") (pin "A3") (pinfunction "IO_1_A3") (pintype "bidirectional"))
      (node (ref "R1") (pin "P$1") (pinfunction "P$1_P$1") (pintype "bidirectional"))
      (node (ref "R45") (pin "P$1") (pinfunction "P$1_P$1") (pintype "bidirectional"))
      (node (ref "SW2") (pin "2") (pinfunction "A1_2") (pintype "bidirectional"))
    )
    (net (code "26") (name "IO2") (class "Default")
      (node (ref "IC1") (pin "A4") (pinfunction "IO_2_A4") (pintype "bidirectional"))
      (node (ref "R44") (pin "P$1") (pinfunction "P$1_P$1") (pintype "bidirectional"))
    )
    (net (code "27") (name "IO3") (class "Default")
      (node (ref "IC1") (pin "A5") (pinfunction "IO_3_A5") (pintype "bidirectional"))
      (node (ref "R43") (pin "P$1") (pinfunction "P$1_P$1") (pintype "bidirectional"))
    )
    (net (code "28") (name "IO4") (class "Default")
      (node (ref "IC1") (pin "A6") (pinfunction "IO_4_A6") (pintype "bidirectional"))
      (node (ref "R42") (pin "P$1") (pinfunction "P$1_P$1") (pintype "bidirectional"))
    )
    (net (code "29") (name "IO5") (class "Default")
      (node (ref "IC1") (pin "A7") (pinfunction "IO_5_A7") (pintype "bidirectional"))
      (node (ref "R41") (pin "P$1") (pinfunction "P$1_P$1") (pintype "bidirectional"))
    )
    (net (code "30") (name "IO6") (class "Default")
      (node (ref "IC1") (pin "A8") (pinfunction "IO_6_A8") (pintype "bidirectional"))
      (node (ref "R40") (pin "P$1") (pinfunction "P$1_P$1") (pintype "bidirectional"))
    )
    (net (code "31") (name "IO7") (class "Default")
      (node (ref "IC1") (pin "A9") (pinfunction "IO_7_A9") (pintype "bidirectional"))
    )
    (net (code "32") (name "IO8") (class "Default")
      (node (ref "IC1") (pin "A10") (pinfunction "IO_8_A10") (pintype "bidirectional"))
    )
    (net (code "33") (name "IO9") (class "Default")
      (node (ref "IC1") (pin "A13") (pinfunction "IO_9_A13") (pintype "bidirectional"))
    )
    (net (code "34") (name "IO10") (class "Default")
      (node (ref "IC1") (pin "A14") (pinfunction "IO_10_A14") (pintype "bidirectional"))
    )
    (net (code "35") (name "IO11") (class "Default")
      (node (ref "IC1") (pin "A15") (pinfunction "IO_11_A15") (pintype "bidirectional"))
    )
    (net (code "36") (name "IO12") (class "Default")
      (node (ref "IC1") (pin "A16") (pinfunction "IO_12_A16") (pintype "bidirectional"))
    )
    (net (code "37") (name "IO13") (class "Default")
      (node (ref "IC1") (pin "A17") (pinfunction "IO_13_A17") (pintype "bidirectional"))
    )
    (net (code "38") (name "IO14") (class "Default")
      (node (ref "IC1") (pin "A18") (pinfunction "IO_14_A18") (pintype "bidirectional"))
    )
    (net (code "39") (name "IO15") (class "Default")
      (node (ref "IC1") (pin "A19") (pinfunction "IO_15_A19") (pintype "bidirectional"))
    )
    (net (code "40") (name "IO16") (class "Default")
      (node (ref "IC1") (pin "A20") (pinfunction "IO_16_A20") (pintype "bidirectional"))
    )
    (net (code "41") (name "IO17") (class "Default")
      (node (ref "IC1") (pin "B1") (pinfunction "IO_17_B1") (pintype "bidirectional"))
    )
    (net (code "42") (name "IO18") (class "Default")
      (node (ref "IC1") (pin "B2") (pinfunction "IO_18_B2") (pintype "bidirectional"))
    )
    (net (code "43") (name "IO19") (class "Default")
      (node (ref "IC1") (pin "B3") (pinfunction "IO_19_B3") (pintype "bidirectional"))
    )
    (net (code "44") (name "IO20") (class "Default")
      (node (ref "IC1") (pin "B4") (pinfunction "IO_20_B4") (pintype "bidirectional"))
    )
    (net (code "45") (name "IO21") (class "Default")
      (node (ref "IC1") (pin "B5") (pinfunction "IO_21_B5") (pintype "bidirectional"))
    )
    (net (code "46") (name "IO22") (class "Default")
      (node (ref "IC1") (pin "B6") (pinfunction "IO_22_B6") (pintype "bidirectional"))
    )
    (net (code "47") (name "IO23") (class "Default")
      (node (ref "IC1") (pin "B7") (pinfunction "IO_23_B7") (pintype "bidirectional"))
    )
    (net (code "48") (name "IO24") (class "Default")
      (node (ref "IC1") (pin "B8") (pinfunction "IO_24_B8") (pintype "bidirectional"))
    )
    (net (code "49") (name "IO25") (class "Default")
      (node (ref "IC1") (pin "B9") (pinfunction "IO_25_B9") (pintype "bidirectional"))
    )
    (net (code "50") (name "IO26") (class "Default")
      (node (ref "IC1") (pin "B10") (pinfunction "IO_26_B10") (pintype "bidirectional"))
    )
    (net (code "51") (name "IO27") (class "Default")
      (node (ref "IC1") (pin "B13") (pinfunction "IO_27_B13") (pintype "bidirectional"))
    )
    (net (code "52") (name "IO28") (class "Default")
      (node (ref "IC1") (pin "B14") (pinfunction "IO_28_B14") (pintype "bidirectional"))
    )
    (net (code "53") (name "IO29") (class "Default")
      (node (ref "IC1") (pin "B15") (pinfunction "IO_29_B15") (pintype "bidirectional"))
    )
    (net (code "54") (name "IO30") (class "Default")
      (node (ref "IC1") (pin "B16") (pinfunction "IO_30_B16") (pintype "bidirectional"))
    )
    (net (code "55") (name "IO31") (class "Default")
      (node (ref "IC1") (pin "B17") (pinfunction "IO_31_B17") (pintype "bidirectional"))
    )
    (net (code "56") (name "IO32") (class "Default")
      (node (ref "IC1") (pin "B18") (pinfunction "IO_32_B18") (pintype "bidirectional"))
    )
    (net (code "57") (name "IO33") (class "Default")
      (node (ref "IC1") (pin "B19") (pinfunction "IO_33_B19") (pintype "bidirectional"))
    )
    (net (code "58") (name "IO34") (class "Default")
      (node (ref "IC1") (pin "B20") (pinfunction "IO_34_B20") (pintype "bidirectional"))
    )
    (net (code "59") (name "IO35") (class "Default")
      (node (ref "IC1") (pin "B21") (pinfunction "IO_35_B21") (pintype "bidirectional"))
    )
    (net (code "60") (name "IO36") (class "Default")
      (node (ref "IC1") (pin "B22") (pinfunction "IO_36_B22") (pintype "bidirectional"))
    )
    (net (code "61") (name "IO37") (class "Default")
      (node (ref "IC1") (pin "C1") (pinfunction "IO_37_C1") (pintype "bidirectional"))
    )
    (net (code "62") (name "IO38") (class "Default")
      (node (ref "IC1") (pin "C2") (pinfunction "IO_38_C2") (pintype "bidirectional"))
    )
    (net (code "63") (name "IO39") (class "Default")
      (node (ref "IC1") (pin "C3") (pinfunction "IO_39_C3") (pintype "bidirectional"))
    )
    (net (code "64") (name "IO40") (class "Default")
      (node (ref "IC1") (pin "C4") (pinfunction "IO_40_C4") (pintype "bidirectional"))
    )
    (net (code "65") (name "IO41") (class "Default")
      (node (ref "IC1") (pin "C6") (pinfunction "IO_41_C6") (pintype "bidirectional"))
    )
    (net (code "66") (name "IO42") (class "Default")
      (node (ref "IC1") (pin "C7") (pinfunction "IO_42_C7") (pintype "bidirectional"))
    )
    (net (code "67") (name "IO43") (class "Default")
      (node (ref "IC1") (pin "C8") (pinfunction "IO_43_C8") (pintype "bidirectional"))
    )
    (net (code "68") (name "IO44") (class "Default")
      (node (ref "IC1") (pin "C10") (pinfunction "IO_44_C10") (pintype "bidirectional"))
    )
    (net (code "69") (name "IO45") (class "Default")
      (node (ref "IC1") (pin "C13") (pinfunction "IO_45_C13") (pintype "bidirectional"))
    )
    (net (code "70") (name "IO46") (class "Default")
      (node (ref "IC1") (pin "C15") (pinfunction "IO_46_C15") (pintype "bidirectional"))
    )
    (net (code "71") (name "IO47") (class "Default")
      (node (ref "IC1") (pin "C17") (pinfunction "IO_47_C17") (pintype "bidirectional"))
    )
    (net (code "72") (name "IO48") (class "Default")
      (node (ref "IC1") (pin "C19") (pinfunction "IO_48_C19") (pintype "bidirectional"))
    )
    (net (code "73") (name "IO49") (class "Default")
      (node (ref "IC1") (pin "C20") (pinfunction "IO_49_C20") (pintype "bidirectional"))
    )
    (net (code "74") (name "IO50") (class "Default")
      (node (ref "IC1") (pin "C21") (pinfunction "IO_50_C21") (pintype "bidirectional"))
    )
    (net (code "75") (name "IO51") (class "Default")
      (node (ref "IC1") (pin "C22") (pinfunction "IO_51_C22") (pintype "bidirectional"))
    )
    (net (code "76") (name "IO53") (class "Default")
      (node (ref "IC1") (pin "D2") (pinfunction "IO_53_D2") (pintype "bidirectional"))
    )
    (net (code "77") (name "IO54") (class "Default")
      (node (ref "IC1") (pin "D6") (pinfunction "IO_54_D6") (pintype "bidirectional"))
    )
    (net (code "78") (name "IO55") (class "Default")
      (node (ref "IC1") (pin "D7") (pinfunction "IO_55_D7") (pintype "bidirectional"))
    )
    (net (code "79") (name "IO56") (class "Default")
      (node (ref "IC1") (pin "D10") (pinfunction "IO_56_D10") (pintype "bidirectional"))
    )
    (net (code "80") (name "IO57") (class "Default")
      (node (ref "IC1") (pin "D13") (pinfunction "IO_57_D13") (pintype "bidirectional"))
    )
    (net (code "81") (name "IO58") (class "Default")
      (node (ref "IC1") (pin "D15") (pinfunction "IO_58_D15") (pintype "bidirectional"))
    )
    (net (code "82") (name "IO59") (class "Default")
      (node (ref "IC1") (pin "D17") (pinfunction "IO_59_D17") (pintype "bidirectional"))
    )
    (net (code "83") (name "IO60") (class "Default")
      (node (ref "IC1") (pin "D19") (pinfunction "IO_60_D19") (pintype "bidirectional"))
    )
    (net (code "84") (name "IO61") (class "Default")
      (node (ref "IC1") (pin "D20") (pinfunction "IO_61_D20") (pintype "bidirectional"))
    )
    (net (code "85") (name "IO62") (class "Default")
      (node (ref "IC1") (pin "D21") (pinfunction "IO_62_D21") (pintype "bidirectional"))
    )
    (net (code "86") (name "IO63") (class "Default")
      (node (ref "IC1") (pin "D22") (pinfunction "IO_63_D22") (pintype "bidirectional"))
    )
    (net (code "87") (name "IO64") (class "Default")
      (node (ref "IC1") (pin "E1") (pinfunction "IO_64_E1") (pintype "bidirectional"))
    )
    (net (code "88") (name "IO66") (class "Default")
      (node (ref "IC1") (pin "E3") (pinfunction "IO_66_E3") (pintype "bidirectional"))
    )
    (net (code "89") (name "IO67") (class "Default")
      (node (ref "IC1") (pin "E4") (pinfunction "IO_67_E4") (pintype "bidirectional"))
    )
    (net (code "90") (name "IO68") (class "Default")
      (node (ref "IC1") (pin "E5") (pinfunction "IO_68_E5") (pintype "bidirectional"))
    )
    (net (code "91") (name "IO69") (class "Default")
      (node (ref "IC1") (pin "E6") (pinfunction "IO_69_E6") (pintype "bidirectional"))
    )
    (net (code "92") (name "IO70") (class "Default")
      (node (ref "IC1") (pin "E7") (pinfunction "IO_70_E7") (pintype "bidirectional"))
    )
    (net (code "93") (name "IO71") (class "Default")
      (node (ref "IC1") (pin "E9") (pinfunction "IO_71_E9") (pintype "bidirectional"))
    )
    (net (code "94") (name "IO72") (class "Default")
      (node (ref "IC1") (pin "E10") (pinfunction "IO_72_E10") (pintype "bidirectional"))
    )
    (net (code "95") (name "IO73") (class "Default")
      (node (ref "IC1") (pin "E11") (pinfunction "IO_73_E11") (pintype "bidirectional"))
    )
    (net (code "96") (name "IO74") (class "Default")
      (node (ref "IC1") (pin "E12") (pinfunction "IO_74_E12") (pintype "bidirectional"))
    )
    (net (code "97") (name "IO75") (class "Default")
      (node (ref "IC1") (pin "E13") (pinfunction "IO_75_E13") (pintype "bidirectional"))
    )
    (net (code "98") (name "IO76") (class "Default")
      (node (ref "IC1") (pin "E14") (pinfunction "IO_76_E14") (pintype "bidirectional"))
    )
    (net (code "99") (name "IO77") (class "Default")
      (node (ref "IC1") (pin "E15") (pinfunction "IO_77_E15") (pintype "bidirectional"))
    )
    (net (code "100") (name "IO78") (class "Default")
      (node (ref "IC1") (pin "E16") (pinfunction "IO_78_E16") (pintype "bidirectional"))
    )
    (net (code "101") (name "IO79") (class "Default")
      (node (ref "IC1") (pin "E21") (pinfunction "IO_79_E21") (pintype "bidirectional"))
    )
    (net (code "102") (name "IO80") (class "Default")
      (node (ref "IC1") (pin "E22") (pinfunction "IO_80_E22") (pintype "bidirectional"))
    )
    (net (code "103") (name "IO81") (class "Default")
      (node (ref "IC1") (pin "F1") (pinfunction "IO_81_F1") (pintype "bidirectional"))
    )
    (net (code "104") (name "IO82") (class "Default")
      (node (ref "IC1") (pin "F2") (pinfunction "IO_82_F2") (pintype "bidirectional"))
    )
    (net (code "105") (name "IO83") (class "Default")
      (node (ref "IC1") (pin "F7") (pinfunction "IO_83_F7") (pintype "bidirectional"))
    )
    (net (code "106") (name "IO84") (class "Default")
      (node (ref "IC1") (pin "F8") (pinfunction "IO_84_F8") (pintype "bidirectional"))
    )
    (net (code "107") (name "IO85") (class "Default")
      (node (ref "IC1") (pin "F9") (pinfunction "IO_85_F9") (pintype "bidirectional"))
    )
    (net (code "108") (name "IO86") (class "Default")
      (node (ref "IC1") (pin "F10") (pinfunction "IO_86_F10") (pintype "bidirectional"))
    )
    (net (code "109") (name "IO87") (class "Default")
      (node (ref "IC1") (pin "F11") (pinfunction "IO_87_F11") (pintype "bidirectional"))
    )
    (net (code "110") (name "IO88") (class "Default")
      (node (ref "IC1") (pin "F13") (pinfunction "IO_88_F13") (pintype "bidirectional"))
    )
    (net (code "111") (name "IO89") (class "Default")
      (node (ref "IC1") (pin "F14") (pinfunction "IO_89_F14") (pintype "bidirectional"))
    )
    (net (code "112") (name "IO90") (class "Default")
      (node (ref "IC1") (pin "F15") (pinfunction "IO_90_F15") (pintype "bidirectional"))
    )
    (net (code "113") (name "IO91") (class "Default")
      (node (ref "IC1") (pin "F16") (pinfunction "IO_91_F16") (pintype "bidirectional"))
    )
    (net (code "114") (name "IO92") (class "Default")
      (node (ref "IC1") (pin "F17") (pinfunction "IO_92_F17") (pintype "bidirectional"))
    )
    (net (code "115") (name "IO93") (class "Default")
      (node (ref "IC1") (pin "F19") (pinfunction "IO_93_F19") (pintype "bidirectional"))
    )
    (net (code "116") (name "IO94") (class "Default")
      (node (ref "IC1") (pin "F20") (pinfunction "IO_94_F20") (pintype "bidirectional"))
    )
    (net (code "117") (name "IO95") (class "Default")
      (node (ref "IC1") (pin "F21") (pinfunction "IO_95_F21") (pintype "bidirectional"))
    )
    (net (code "118") (name "IO96") (class "Default")
      (node (ref "IC1") (pin "F22") (pinfunction "IO_96_F22") (pintype "bidirectional"))
    )
    (net (code "119") (name "IO97") (class "Default")
      (node (ref "IC1") (pin "G3") (pinfunction "IO_97_G3") (pintype "bidirectional"))
    )
    (net (code "120") (name "IO98") (class "Default")
      (node (ref "IC1") (pin "G4") (pinfunction "IO_98_G4") (pintype "bidirectional"))
    )
    (net (code "121") (name "IO99") (class "Default")
      (node (ref "IC1") (pin "G5") (pinfunction "IO_99_G5") (pintype "bidirectional"))
    )
    (net (code "122") (name "IO100") (class "Default")
      (node (ref "IC1") (pin "G7") (pinfunction "IO_100_G7") (pintype "bidirectional"))
    )
    (net (code "123") (name "IO101") (class "Default")
      (node (ref "IC1") (pin "G8") (pinfunction "IO_101_G8") (pintype "bidirectional"))
    )
    (net (code "124") (name "IO102") (class "Default")
      (node (ref "IC1") (pin "G9") (pinfunction "IO_102_G9") (pintype "bidirectional"))
    )
    (net (code "125") (name "IO103") (class "Default")
      (node (ref "IC1") (pin "G10") (pinfunction "IO_103_G10") (pintype "bidirectional"))
    )
    (net (code "126") (name "IO104") (class "Default")
      (node (ref "IC1") (pin "G11") (pinfunction "IO_104_G11") (pintype "bidirectional"))
    )
    (net (code "127") (name "IO105") (class "Default")
      (node (ref "IC1") (pin "G13") (pinfunction "IO_105_G13") (pintype "bidirectional"))
    )
    (net (code "128") (name "IO106") (class "Default")
      (node (ref "IC1") (pin "G14") (pinfunction "IO_106_G14") (pintype "bidirectional"))
    )
    (net (code "129") (name "IO107") (class "Default")
      (node (ref "IC1") (pin "G15") (pinfunction "IO_107_G15") (pintype "bidirectional"))
    )
    (net (code "130") (name "IO108") (class "Default")
      (node (ref "IC1") (pin "G16") (pinfunction "IO_108_G16") (pintype "bidirectional"))
    )
    (net (code "131") (name "IO109") (class "Default")
      (node (ref "IC1") (pin "G17") (pinfunction "IO_109_G17") (pintype "bidirectional"))
    )
    (net (code "132") (name "IO110") (class "Default")
      (node (ref "IC1") (pin "G18") (pinfunction "IO_110_G18") (pintype "bidirectional"))
    )
    (net (code "133") (name "IO111") (class "Default")
      (node (ref "IC1") (pin "H1") (pinfunction "IO_111_H1") (pintype "bidirectional"))
    )
    (net (code "134") (name "IO112") (class "Default")
      (node (ref "IC1") (pin "H2") (pinfunction "IO_112_H2") (pintype "bidirectional"))
    )
    (net (code "135") (name "IO113") (class "Default")
      (node (ref "IC1") (pin "H5") (pinfunction "IO_113_H5") (pintype "bidirectional"))
    )
    (net (code "136") (name "IO114") (class "Default")
      (node (ref "IC1") (pin "H6") (pinfunction "IO_114_H6") (pintype "bidirectional"))
    )
    (net (code "137") (name "IO115") (class "Default")
      (node (ref "IC1") (pin "H7") (pinfunction "IO_115_H7") (pintype "bidirectional"))
    )
    (net (code "138") (name "IO116") (class "Default")
      (node (ref "IC1") (pin "H8") (pinfunction "IO_116_H8") (pintype "bidirectional"))
    )
    (net (code "139") (name "IO117") (class "Default")
      (node (ref "IC1") (pin "H10") (pinfunction "IO_117_H10") (pintype "bidirectional"))
    )
    (net (code "140") (name "IO118") (class "Default")
      (node (ref "IC1") (pin "H11") (pinfunction "IO_118_H11") (pintype "bidirectional"))
    )
    (net (code "141") (name "IO119") (class "Default")
      (node (ref "IC1") (pin "H14") (pinfunction "IO_119_H14") (pintype "bidirectional"))
    )
    (net (code "142") (name "IO120") (class "Default")
      (node (ref "IC1") (pin "H15") (pinfunction "IO_120_H15") (pintype "bidirectional"))
    )
    (net (code "143") (name "IO121") (class "Default")
      (node (ref "IC1") (pin "H16") (pinfunction "IO_121_H16") (pintype "bidirectional"))
    )
    (net (code "144") (name "IO122") (class "Default")
      (node (ref "IC1") (pin "H17") (pinfunction "IO_122_H17") (pintype "bidirectional"))
    )
    (net (code "145") (name "IO123") (class "Default")
      (node (ref "IC1") (pin "H18") (pinfunction "IO_123_H18") (pintype "bidirectional"))
    )
    (net (code "146") (name "IO124") (class "Default")
      (node (ref "IC1") (pin "H19") (pinfunction "IO_124_H19") (pintype "bidirectional"))
    )
    (net (code "147") (name "IO125") (class "Default")
      (node (ref "IC1") (pin "H20") (pinfunction "IO_125_H20") (pintype "bidirectional"))
    )
    (net (code "148") (name "IO126") (class "Default")
      (node (ref "IC1") (pin "H21") (pinfunction "IO_126_H21") (pintype "bidirectional"))
    )
    (net (code "149") (name "IO127") (class "Default")
      (node (ref "IC1") (pin "H22") (pinfunction "IO_127_H22") (pintype "bidirectional"))
    )
    (net (code "150") (name "IO128") (class "Default")
      (node (ref "IC1") (pin "J1") (pinfunction "IO_128_J1") (pintype "bidirectional"))
    )
    (net (code "151") (name "IO129") (class "Default")
      (node (ref "IC1") (pin "J2") (pinfunction "IO_129_J2") (pintype "bidirectional"))
    )
    (net (code "152") (name "IO130") (class "Default")
      (node (ref "IC1") (pin "J3") (pinfunction "IO_130_J3") (pintype "bidirectional"))
    )
    (net (code "153") (name "IO131") (class "Default")
      (node (ref "IC1") (pin "J4") (pinfunction "IO_131_J4") (pintype "bidirectional"))
    )
    (net (code "154") (name "IO132") (class "Default")
      (node (ref "IC1") (pin "J5") (pinfunction "IO_132_J5") (pintype "bidirectional"))
    )
    (net (code "155") (name "IO133") (class "Default")
      (node (ref "IC1") (pin "J6") (pinfunction "IO_133_J6") (pintype "bidirectional"))
    )
    (net (code "156") (name "IO134") (class "Default")
      (node (ref "IC1") (pin "J7") (pinfunction "IO_134_J7") (pintype "bidirectional"))
    )
    (net (code "157") (name "IO135") (class "Default")
      (node (ref "IC1") (pin "J8") (pinfunction "IO_135_J8") (pintype "bidirectional"))
    )
    (net (code "158") (name "IO136") (class "Default")
      (node (ref "IC1") (pin "J17") (pinfunction "IO_136_J17") (pintype "bidirectional"))
    )
    (net (code "159") (name "IO137") (class "Default")
      (node (ref "IC1") (pin "J18") (pinfunction "IO_137_J18") (pintype "bidirectional"))
    )
    (net (code "160") (name "IO138") (class "Default")
      (node (ref "IC1") (pin "J21") (pinfunction "IO_138_J21") (pintype "bidirectional"))
    )
    (net (code "161") (name "IO139") (class "Default")
      (node (ref "IC1") (pin "J22") (pinfunction "IO_139_J22") (pintype "bidirectional"))
    )
    (net (code "162") (name "IO141") (class "Default")
      (node (ref "IC1") (pin "K7") (pinfunction "IO_141_K7") (pintype "bidirectional"))
    )
    (net (code "163") (name "IO142") (class "Default")
      (node (ref "IC1") (pin "K8") (pinfunction "IO_142_K8") (pintype "bidirectional"))
    )
    (net (code "164") (name "IO143") (class "Default")
      (node (ref "IC1") (pin "K17") (pinfunction "IO_143_K17") (pintype "bidirectional"))
    )
    (net (code "165") (name "IO144") (class "Default")
      (node (ref "IC1") (pin "K18") (pinfunction "IO_144_K18") (pintype "bidirectional"))
    )
    (net (code "166") (name "IO145") (class "Default")
      (node (ref "IC1") (pin "K19") (pinfunction "IO_145_K19") (pintype "bidirectional"))
    )
    (net (code "167") (name "IO146") (class "Default")
      (node (ref "IC1") (pin "K21") (pinfunction "IO_146_K21") (pintype "bidirectional"))
    )
    (net (code "168") (name "IO147") (class "Default")
      (node (ref "IC1") (pin "K22") (pinfunction "IO_147_K22") (pintype "bidirectional"))
    )
    (net (code "169") (name "IO148") (class "Default")
      (node (ref "IC1") (pin "L6") (pinfunction "IO_148_L6") (pintype "bidirectional"))
    )
    (net (code "170") (name "IO149") (class "Default")
      (node (ref "IC1") (pin "L7") (pinfunction "IO_149_L7") (pintype "bidirectional"))
    )
    (net (code "171") (name "IO150") (class "Default")
      (node (ref "IC1") (pin "L8") (pinfunction "IO_150_L8") (pintype "bidirectional"))
    )
    (net (code "172") (name "IO151") (class "Default")
      (node (ref "IC1") (pin "L21") (pinfunction "IO_151_L21") (pintype "bidirectional"))
    )
    (net (code "173") (name "IO152") (class "Default")
      (node (ref "IC1") (pin "L22") (pinfunction "IO_152_L22") (pintype "bidirectional"))
    )
    (net (code "174") (name "IO153") (class "Default")
      (node (ref "IC1") (pin "M1") (pinfunction "IO_153_M1") (pintype "bidirectional"))
    )
    (net (code "175") (name "IO154") (class "Default")
      (node (ref "IC1") (pin "M2") (pinfunction "IO_154_M2") (pintype "bidirectional"))
    )
    (net (code "176") (name "IO155") (class "Default")
      (node (ref "IC1") (pin "M3") (pinfunction "IO_155_M3") (pintype "bidirectional"))
    )
    (net (code "177") (name "IO156") (class "Default")
      (node (ref "IC1") (pin "M4") (pinfunction "IO_156_M4") (pintype "bidirectional"))
    )
    (net (code "178") (name "IO157") (class "Default")
      (node (ref "IC1") (pin "M5") (pinfunction "IO_157_M5") (pintype "bidirectional"))
    )
    (net (code "179") (name "IO158") (class "Default")
      (node (ref "IC1") (pin "M6") (pinfunction "IO_158_M6") (pintype "bidirectional"))
    )
    (net (code "180") (name "IO159") (class "Default")
      (node (ref "IC1") (pin "M7") (pinfunction "IO_159_M7") (pintype "bidirectional"))
    )
    (net (code "181") (name "IO160") (class "Default")
      (node (ref "IC1") (pin "M8") (pinfunction "IO_160_M8") (pintype "bidirectional"))
    )
    (net (code "182") (name "IO161") (class "Default")
      (node (ref "IC1") (pin "M16") (pinfunction "IO_161_M16") (pintype "bidirectional"))
    )
    (net (code "183") (name "IO162") (class "Default")
      (node (ref "IC1") (pin "M19") (pinfunction "IO_162_M19") (pintype "bidirectional"))
    )
    (net (code "184") (name "IO163") (class "Default")
      (node (ref "IC1") (pin "M20") (pinfunction "IO_163_M20") (pintype "bidirectional"))
    )
    (net (code "185") (name "IO164") (class "Default")
      (node (ref "IC1") (pin "M21") (pinfunction "IO_164_M21") (pintype "bidirectional"))
    )
    (net (code "186") (name "IO165") (class "Default")
      (node (ref "IC1") (pin "M22") (pinfunction "IO_165_M22") (pintype "bidirectional"))
    )
    (net (code "187") (name "IO166") (class "Default")
      (node (ref "IC1") (pin "N1") (pinfunction "IO_166_N1") (pintype "bidirectional"))
    )
    (net (code "188") (name "IO167") (class "Default")
      (node (ref "IC1") (pin "N2") (pinfunction "IO_167_N2") (pintype "bidirectional"))
    )
    (net (code "189") (name "IO168") (class "Default")
      (node (ref "IC1") (pin "N5") (pinfunction "IO_168_N5") (pintype "bidirectional"))
    )
    (net (code "190") (name "IO169") (class "Default")
      (node (ref "IC1") (pin "N6") (pinfunction "IO_169_N6") (pintype "bidirectional"))
    )
    (net (code "191") (name "IO170") (class "Default")
      (node (ref "IC1") (pin "N7") (pinfunction "IO_170_N7") (pintype "bidirectional"))
    )
    (net (code "192") (name "IO171") (class "Default")
      (node (ref "IC1") (pin "N8") (pinfunction "IO_171_N8") (pintype "bidirectional"))
    )
    (net (code "193") (name "IO172") (class "Default")
      (node (ref "IC1") (pin "N16") (pinfunction "IO_172_N16") (pintype "bidirectional"))
    )
    (net (code "194") (name "IO173") (class "Default")
      (node (ref "IC1") (pin "N17") (pinfunction "IO_173_N17") (pintype "bidirectional"))
    )
    (net (code "195") (name "IO174") (class "Default")
      (node (ref "IC1") (pin "N18") (pinfunction "IO_174_N18") (pintype "bidirectional"))
    )
    (net (code "196") (name "IO175") (class "Default")
      (node (ref "IC1") (pin "N19") (pinfunction "IO_175_N19") (pintype "bidirectional"))
    )
    (net (code "197") (name "IO176") (class "Default")
      (node (ref "IC1") (pin "N20") (pinfunction "IO_176_N20") (pintype "bidirectional"))
    )
    (net (code "198") (name "IO177") (class "Default")
      (node (ref "IC1") (pin "N21") (pinfunction "IO_177_N21") (pintype "bidirectional"))
    )
    (net (code "199") (name "IO178") (class "Default")
      (node (ref "IC1") (pin "N22") (pinfunction "IO_178_N22") (pintype "bidirectional"))
    )
    (net (code "200") (name "IO179") (class "Default")
      (node (ref "IC1") (pin "P1") (pinfunction "IO_179_P1") (pintype "bidirectional"))
    )
    (net (code "201") (name "IO180") (class "Default")
      (node (ref "IC1") (pin "P2") (pinfunction "IO_180_P2") (pintype "bidirectional"))
    )
    (net (code "202") (name "IO181") (class "Default")
      (node (ref "IC1") (pin "P3") (pinfunction "IO_181_P3") (pintype "bidirectional"))
    )
    (net (code "203") (name "IO182") (class "Default")
      (node (ref "IC1") (pin "P4") (pinfunction "IO_182_P4") (pintype "bidirectional"))
    )
    (net (code "204") (name "IO183") (class "Default")
      (node (ref "IC1") (pin "P5") (pinfunction "IO_183_P5") (pintype "bidirectional"))
    )
    (net (code "205") (name "IO184") (class "Default")
      (node (ref "IC1") (pin "P6") (pinfunction "IO_184_P6") (pintype "bidirectional"))
    )
    (net (code "206") (name "IO185") (class "Default")
      (node (ref "IC1") (pin "P7") (pinfunction "IO_185_P7") (pintype "bidirectional"))
    )
    (net (code "207") (name "IO186") (class "Default")
      (node (ref "IC1") (pin "P15") (pinfunction "IO_186_P15") (pintype "bidirectional"))
    )
    (net (code "208") (name "IO187") (class "Default")
      (node (ref "IC1") (pin "P16") (pinfunction "IO_187_P16") (pintype "bidirectional"))
    )
    (net (code "209") (name "IO188") (class "Default")
      (node (ref "IC1") (pin "P17") (pinfunction "IO_188_P17") (pintype "bidirectional"))
    )
    (net (code "210") (name "IO189") (class "Default")
      (node (ref "IC1") (pin "P20") (pinfunction "IO_189_P20") (pintype "bidirectional"))
    )
    (net (code "211") (name "IO190") (class "Default")
      (node (ref "IC1") (pin "P21") (pinfunction "IO_190_P21") (pintype "bidirectional"))
    )
    (net (code "212") (name "IO191") (class "Default")
      (node (ref "IC1") (pin "P22") (pinfunction "IO_191_P22") (pintype "bidirectional"))
    )
    (net (code "213") (name "IO192") (class "Default")
      (node (ref "IC1") (pin "R1") (pinfunction "IO_192_R1") (pintype "bidirectional"))
    )
    (net (code "214") (name "IO193") (class "Default")
      (node (ref "IC1") (pin "R2") (pinfunction "IO_193_R2") (pintype "bidirectional"))
    )
    (net (code "215") (name "IO194") (class "Default")
      (node (ref "IC1") (pin "R5") (pinfunction "IO_194_R5") (pintype "bidirectional"))
    )
    (net (code "216") (name "IO195") (class "Default")
      (node (ref "IC1") (pin "R6") (pinfunction "IO_195_R6") (pintype "bidirectional"))
    )
    (net (code "217") (name "IO196") (class "Default")
      (node (ref "IC1") (pin "R7") (pinfunction "IO_196_R7") (pintype "bidirectional"))
    )
    (net (code "218") (name "IO197") (class "Default")
      (node (ref "IC1") (pin "R14") (pinfunction "IO_197_R14") (pintype "bidirectional"))
    )
    (net (code "219") (name "IO198") (class "Default")
      (node (ref "IC1") (pin "R15") (pinfunction "IO_198_R15") (pintype "bidirectional"))
    )
    (net (code "220") (name "IO199") (class "Default")
      (node (ref "IC1") (pin "R16") (pinfunction "IO_199_R16") (pintype "bidirectional"))
    )
    (net (code "221") (name "IO200") (class "Default")
      (node (ref "IC1") (pin "R17") (pinfunction "IO_200_R17") (pintype "bidirectional"))
    )
    (net (code "222") (name "IO201") (class "Default")
      (node (ref "IC1") (pin "R18") (pinfunction "IO_201_R18") (pintype "bidirectional"))
    )
    (net (code "223") (name "IO202") (class "Default")
      (node (ref "IC1") (pin "R19") (pinfunction "IO_202_R19") (pintype "bidirectional"))
    )
    (net (code "224") (name "IO203") (class "Default")
      (node (ref "IC1") (pin "R20") (pinfunction "IO_203_R20") (pintype "bidirectional"))
    )
    (net (code "225") (name "IO204") (class "Default")
      (node (ref "IC1") (pin "R21") (pinfunction "IO_204_R21") (pintype "bidirectional"))
    )
    (net (code "226") (name "IO205") (class "Default")
      (node (ref "IC1") (pin "R22") (pinfunction "IO_205_R22") (pintype "bidirectional"))
    )
    (net (code "227") (name "IO206") (class "Default")
      (node (ref "IC1") (pin "T3") (pinfunction "IO_206_T3") (pintype "bidirectional"))
    )
    (net (code "228") (name "IO207") (class "Default")
      (node (ref "IC1") (pin "T4") (pinfunction "IO_207_T4") (pintype "bidirectional"))
    )
    (net (code "229") (name "IO208") (class "Default")
      (node (ref "IC1") (pin "T5") (pinfunction "IO_208_T5") (pintype "bidirectional"))
    )
    (net (code "230") (name "IO209") (class "Default")
      (node (ref "IC1") (pin "T7") (pinfunction "IO_209_T7") (pintype "bidirectional"))
    )
    (net (code "231") (name "IO210") (class "Default")
      (node (ref "IC1") (pin "T8") (pinfunction "IO_210_T8") (pintype "bidirectional"))
    )
    (net (code "232") (name "IO211") (class "Default")
      (node (ref "IC1") (pin "T9") (pinfunction "IO_211_T9") (pintype "bidirectional"))
    )
    (net (code "233") (name "IO212") (class "Default")
      (node (ref "IC1") (pin "T10") (pinfunction "IO_212_T10") (pintype "bidirectional"))
    )
    (net (code "234") (name "IO213") (class "Default")
      (node (ref "IC1") (pin "T11") (pinfunction "IO_213_T11") (pintype "bidirectional"))
    )
    (net (code "235") (name "IO214") (class "Default")
      (node (ref "IC1") (pin "T12") (pinfunction "IO_214_T12") (pintype "bidirectional"))
    )
    (net (code "236") (name "IO215") (class "Default")
      (node (ref "IC1") (pin "T13") (pinfunction "IO_215_T13") (pintype "bidirectional"))
    )
    (net (code "237") (name "IO216") (class "Default")
      (node (ref "IC1") (pin "T14") (pinfunction "IO_216_T14") (pintype "bidirectional"))
    )
    (net (code "238") (name "IO217") (class "Default")
      (node (ref "IC1") (pin "T15") (pinfunction "IO_217_T15") (pintype "bidirectional"))
    )
    (net (code "239") (name "IO218") (class "Default")
      (node (ref "IC1") (pin "T16") (pinfunction "IO_218_T16") (pintype "bidirectional"))
    )
    (net (code "240") (name "IO219") (class "Default")
      (node (ref "IC1") (pin "T17") (pinfunction "IO_219_T17") (pintype "bidirectional"))
    )
    (net (code "241") (name "IO220") (class "Default")
      (node (ref "IC1") (pin "T18") (pinfunction "IO_220_T18") (pintype "bidirectional"))
    )
    (net (code "242") (name "IO221") (class "Default")
      (node (ref "IC1") (pin "U1") (pinfunction "IO_221_U1") (pintype "bidirectional"))
    )
    (net (code "243") (name "IO222") (class "Default")
      (node (ref "IC1") (pin "U2") (pinfunction "IO_222_U2") (pintype "bidirectional"))
    )
    (net (code "244") (name "IO223") (class "Default")
      (node (ref "IC1") (pin "U7") (pinfunction "IO_223_U7") (pintype "bidirectional"))
    )
    (net (code "245") (name "IO224") (class "Default")
      (node (ref "IC1") (pin "U8") (pinfunction "IO_224_U8") (pintype "bidirectional"))
    )
    (net (code "246") (name "IO225") (class "Default")
      (node (ref "IC1") (pin "U9") (pinfunction "IO_225_U9") (pintype "bidirectional"))
    )
    (net (code "247") (name "IO226") (class "Default")
      (node (ref "IC1") (pin "U10") (pinfunction "IO_226_U10") (pintype "bidirectional"))
    )
    (net (code "248") (name "IO227") (class "Default")
      (node (ref "IC1") (pin "U11") (pinfunction "IO_227_U11") (pintype "bidirectional"))
    )
    (net (code "249") (name "IO228") (class "Default")
      (node (ref "IC1") (pin "U12") (pinfunction "IO_228_U12") (pintype "bidirectional"))
    )
    (net (code "250") (name "IO229") (class "Default")
      (node (ref "IC1") (pin "U13") (pinfunction "IO_229_U13") (pintype "bidirectional"))
    )
    (net (code "251") (name "IO230") (class "Default")
      (node (ref "IC1") (pin "U14") (pinfunction "IO_230_U14") (pintype "bidirectional"))
    )
    (net (code "252") (name "IO231") (class "Default")
      (node (ref "IC1") (pin "U15") (pinfunction "IO_231_U15") (pintype "bidirectional"))
    )
    (net (code "253") (name "IO232") (class "Default")
      (node (ref "IC1") (pin "U16") (pinfunction "IO_232_U16") (pintype "bidirectional"))
    )
    (net (code "254") (name "IO233") (class "Default")
      (node (ref "IC1") (pin "U17") (pinfunction "IO_233_U17") (pintype "bidirectional"))
    )
    (net (code "255") (name "IO234") (class "Default")
      (node (ref "IC1") (pin "U19") (pinfunction "IO_234_U19") (pintype "bidirectional"))
    )
    (net (code "256") (name "IO235") (class "Default")
      (node (ref "IC1") (pin "U20") (pinfunction "IO_235_U20") (pintype "bidirectional"))
    )
    (net (code "257") (name "IO236") (class "Default")
      (node (ref "IC1") (pin "U21") (pinfunction "IO_236_U21") (pintype "bidirectional"))
    )
    (net (code "258") (name "IO237") (class "Default")
      (node (ref "IC1") (pin "U22") (pinfunction "IO_237_U22") (pintype "bidirectional"))
    )
    (net (code "259") (name "IO238") (class "Default")
      (node (ref "IC1") (pin "V1") (pinfunction "IO_238_V1") (pintype "bidirectional"))
    )
    (net (code "260") (name "IO239") (class "Default")
      (node (ref "IC1") (pin "V2") (pinfunction "IO_239_V2") (pintype "bidirectional"))
    )
    (net (code "261") (name "IO240") (class "Default")
      (node (ref "IC1") (pin "V3") (pinfunction "IO_240_V3") (pintype "bidirectional"))
    )
    (net (code "262") (name "IO241") (class "Default")
      (node (ref "IC1") (pin "V4") (pinfunction "IO_241_V4") (pintype "bidirectional"))
    )
    (net (code "263") (name "IO242") (class "Default")
      (node (ref "IC1") (pin "V5") (pinfunction "IO_242_V5") (pintype "bidirectional"))
    )
    (net (code "264") (name "IO243") (class "Default")
      (node (ref "IC1") (pin "V6") (pinfunction "IO_243_V6") (pintype "bidirectional"))
    )
    (net (code "265") (name "IO244") (class "Default")
      (node (ref "IC1") (pin "V7") (pinfunction "IO_244_V7") (pintype "bidirectional"))
    )
    (net (code "266") (name "IO245") (class "Default")
      (node (ref "IC1") (pin "V8") (pinfunction "IO_245_V8") (pintype "bidirectional"))
    )
    (net (code "267") (name "IO246") (class "Default")
      (node (ref "IC1") (pin "V9") (pinfunction "IO_246_V9") (pintype "bidirectional"))
    )
    (net (code "268") (name "IO247") (class "Default")
      (node (ref "IC1") (pin "V10") (pinfunction "IO_247_V10") (pintype "bidirectional"))
    )
    (net (code "269") (name "IO248") (class "Default")
      (node (ref "IC1") (pin "V11") (pinfunction "IO_248_V11") (pintype "bidirectional"))
    )
    (net (code "270") (name "IO249") (class "Default")
      (node (ref "IC1") (pin "V12") (pinfunction "IO_249_V12") (pintype "bidirectional"))
    )
    (net (code "271") (name "IO250") (class "Default")
      (node (ref "IC1") (pin "V13") (pinfunction "IO_250_V13") (pintype "bidirectional"))
    )
    (net (code "272") (name "IO251") (class "Default")
      (node (ref "IC1") (pin "V14") (pinfunction "IO_251_V14") (pintype "bidirectional"))
    )
    (net (code "273") (name "IO252") (class "Default")
      (node (ref "IC1") (pin "V15") (pinfunction "IO_252_V15") (pintype "bidirectional"))
    )
    (net (code "274") (name "IO253") (class "Default")
      (node (ref "IC1") (pin "V16") (pinfunction "IO_253_V16") (pintype "bidirectional"))
    )
    (net (code "275") (name "IO254") (class "Default")
      (node (ref "IC1") (pin "V21") (pinfunction "IO_254_V21") (pintype "bidirectional"))
    )
    (net (code "276") (name "IO255") (class "Default")
      (node (ref "IC1") (pin "V22") (pinfunction "IO_255_V22") (pintype "bidirectional"))
    )
    (net (code "277") (name "IO256") (class "Default")
      (node (ref "IC1") (pin "W1") (pinfunction "IO_256_W1") (pintype "bidirectional"))
    )
    (net (code "278") (name "IO257") (class "Default")
      (node (ref "IC1") (pin "W2") (pinfunction "IO_257_W2") (pintype "bidirectional"))
    )
    (net (code "279") (name "IO258") (class "Default")
      (node (ref "IC1") (pin "W6") (pinfunction "IO_258_W6") (pintype "bidirectional"))
    )
    (net (code "280") (name "IO259") (class "Default")
      (node (ref "IC1") (pin "W7") (pinfunction "IO_259_W7") (pintype "bidirectional"))
    )
    (net (code "281") (name "IO260") (class "Default")
      (node (ref "IC1") (pin "W8") (pinfunction "IO_260_W8") (pintype "bidirectional"))
    )
    (net (code "282") (name "IO261") (class "Default")
      (node (ref "IC1") (pin "W10") (pinfunction "IO_261_W10") (pintype "bidirectional"))
    )
    (net (code "283") (name "IO262") (class "Default")
      (node (ref "IC1") (pin "W13") (pinfunction "IO_262_W13") (pintype "bidirectional"))
    )
    (net (code "284") (name "IO263") (class "Default")
      (node (ref "IC1") (pin "W14") (pinfunction "IO_263_W14") (pintype "bidirectional"))
    )
    (net (code "285") (name "IO264") (class "Default")
      (node (ref "IC1") (pin "W15") (pinfunction "IO_264_W15") (pintype "bidirectional"))
    )
    (net (code "286") (name "IO265") (class "Default")
      (node (ref "IC1") (pin "W17") (pinfunction "IO_265_W17") (pintype "bidirectional"))
    )
    (net (code "287") (name "IO266") (class "Default")
      (node (ref "IC1") (pin "W19") (pinfunction "IO_266_W19") (pintype "bidirectional"))
    )
    (net (code "288") (name "IO267") (class "Default")
      (node (ref "IC1") (pin "W20") (pinfunction "IO_267_W20") (pintype "bidirectional"))
    )
    (net (code "289") (name "IO268") (class "Default")
      (node (ref "IC1") (pin "W21") (pinfunction "IO_268_W21") (pintype "bidirectional"))
    )
    (net (code "290") (name "IO269") (class "Default")
      (node (ref "IC1") (pin "W22") (pinfunction "IO_269_W22") (pintype "bidirectional"))
    )
    (net (code "291") (name "IO270") (class "Default")
      (node (ref "IC1") (pin "Y1") (pinfunction "IO_270_Y1") (pintype "bidirectional"))
    )
    (net (code "292") (name "IO271") (class "Default")
      (node (ref "IC1") (pin "Y2") (pinfunction "IO_271_Y2") (pintype "bidirectional"))
    )
    (net (code "293") (name "IO272") (class "Default")
      (node (ref "IC1") (pin "Y3") (pinfunction "IO_272_Y3") (pintype "bidirectional"))
    )
    (net (code "294") (name "IO273") (class "Default")
      (node (ref "IC1") (pin "Y4") (pinfunction "IO_273_Y4") (pintype "bidirectional"))
    )
    (net (code "295") (name "IO274") (class "Default")
      (node (ref "IC1") (pin "Y6") (pinfunction "IO_274_Y6") (pintype "bidirectional"))
    )
    (net (code "296") (name "IO275") (class "Default")
      (node (ref "IC1") (pin "Y7") (pinfunction "IO_275_Y7") (pintype "bidirectional"))
    )
    (net (code "297") (name "IO276") (class "Default")
      (node (ref "IC1") (pin "Y8") (pinfunction "IO_276_Y8") (pintype "bidirectional"))
    )
    (net (code "298") (name "IO277") (class "Default")
      (node (ref "IC1") (pin "Y10") (pinfunction "IO_277_Y10") (pintype "bidirectional"))
    )
    (net (code "299") (name "IO278") (class "Default")
      (node (ref "IC1") (pin "Y13") (pinfunction "IO_278_Y13") (pintype "bidirectional"))
    )
    (net (code "300") (name "IO279") (class "Default")
      (node (ref "IC1") (pin "Y17") (pinfunction "IO_279_Y17") (pintype "bidirectional"))
    )
    (net (code "301") (name "IO280") (class "Default")
      (node (ref "IC1") (pin "Y21") (pinfunction "IO_280_Y21") (pintype "bidirectional"))
    )
    (net (code "302") (name "IO281") (class "Default")
      (node (ref "IC1") (pin "Y22") (pinfunction "IO_281_Y22") (pintype "bidirectional"))
    )
    (net (code "303") (name "IO282") (class "Default")
      (node (ref "IC1") (pin "AA1") (pinfunction "IO_282_AA1") (pintype "bidirectional"))
    )
    (net (code "304") (name "IO283") (class "Default")
      (node (ref "IC1") (pin "AA3") (pinfunction "IO_283_AA3") (pintype "bidirectional"))
    )
    (net (code "305") (name "IO284") (class "Default")
      (node (ref "IC1") (pin "AA4") (pinfunction "IO_284_AA4") (pintype "bidirectional"))
    )
    (net (code "306") (name "IO285") (class "Default")
      (node (ref "IC1") (pin "AA5") (pinfunction "IO_285_AA5") (pintype "bidirectional"))
    )
    (net (code "307") (name "IO286") (class "Default")
      (node (ref "IC1") (pin "AA7") (pinfunction "IO_286_AA7") (pintype "bidirectional"))
    )
    (net (code "308") (name "IO287") (class "Default")
      (node (ref "IC1") (pin "AA8") (pinfunction "IO_287_AA8") (pintype "bidirectional"))
    )
    (net (code "309") (name "IO288") (class "Default")
      (node (ref "IC1") (pin "AA9") (pinfunction "IO_288_AA9") (pintype "bidirectional"))
    )
    (net (code "310") (name "IO289") (class "Default")
      (node (ref "IC1") (pin "AA10") (pinfunction "IO_289_AA10") (pintype "bidirectional"))
    )
    (net (code "311") (name "IO290") (class "Default")
      (node (ref "IC1") (pin "AA13") (pinfunction "IO_290_AA13") (pintype "bidirectional"))
    )
    (net (code "312") (name "IO291") (class "Default")
      (node (ref "IC1") (pin "AA14") (pinfunction "IO_291_AA14") (pintype "bidirectional"))
    )
    (net (code "313") (name "IO292") (class "Default")
      (node (ref "IC1") (pin "AA15") (pinfunction "IO_292_AA15") (pintype "bidirectional"))
    )
    (net (code "314") (name "IO293") (class "Default")
      (node (ref "IC1") (pin "AA16") (pinfunction "IO_293_AA16") (pintype "bidirectional"))
    )
    (net (code "315") (name "IO294") (class "Default")
      (node (ref "IC1") (pin "AA17") (pinfunction "IO_294_AA17") (pintype "bidirectional"))
    )
    (net (code "316") (name "IO295") (class "Default")
      (node (ref "IC1") (pin "AA18") (pinfunction "IO_295_AA18") (pintype "bidirectional"))
    )
    (net (code "317") (name "IO296") (class "Default")
      (node (ref "IC1") (pin "AA19") (pinfunction "IO_296_AA19") (pintype "bidirectional"))
    )
    (net (code "318") (name "IO297") (class "Default")
      (node (ref "IC1") (pin "AA20") (pinfunction "IO_297_AA20") (pintype "bidirectional"))
    )
    (net (code "319") (name "IO298") (class "Default")
      (node (ref "IC1") (pin "AA21") (pinfunction "IO_298_AA21") (pintype "bidirectional"))
    )
    (net (code "320") (name "IO299") (class "Default")
      (node (ref "IC1") (pin "AB3") (pinfunction "IO_299_AB3") (pintype "bidirectional"))
    )
    (net (code "321") (name "IO300") (class "Default")
      (node (ref "IC1") (pin "AB4") (pinfunction "IO_300_AB4") (pintype "bidirectional"))
    )
    (net (code "322") (name "IO301") (class "Default")
      (node (ref "IC1") (pin "AB5") (pinfunction "IO_301_AB5") (pintype "bidirectional"))
    )
    (net (code "323") (name "IO302") (class "Default")
      (node (ref "IC1") (pin "AB7") (pinfunction "IO_302_AB7") (pintype "bidirectional"))
    )
    (net (code "324") (name "IO303") (class "Default")
      (node (ref "IC1") (pin "AB8") (pinfunction "IO_303_AB8") (pintype "bidirectional"))
    )
    (net (code "325") (name "IO304") (class "Default")
      (node (ref "IC1") (pin "AB9") (pinfunction "IO_304_AB9") (pintype "bidirectional"))
    )
    (net (code "326") (name "IO305") (class "Default")
      (node (ref "IC1") (pin "AB10") (pinfunction "IO_305_AB10") (pintype "bidirectional"))
    )
    (net (code "327") (name "IO306") (class "Default")
      (node (ref "IC1") (pin "AB13") (pinfunction "IO_306_AB13") (pintype "bidirectional"))
    )
    (net (code "328") (name "IO307") (class "Default")
      (node (ref "IC1") (pin "AB14") (pinfunction "IO_307_AB14") (pintype "bidirectional"))
    )
    (net (code "329") (name "IO308") (class "Default")
      (node (ref "IC1") (pin "AB15") (pinfunction "IO_308_AB15") (pintype "bidirectional"))
    )
    (net (code "330") (name "IO309") (class "Default")
      (node (ref "IC1") (pin "AB16") (pinfunction "IO_309_AB16") (pintype "bidirectional"))
    )
    (net (code "331") (name "IO310") (class "Default")
      (node (ref "IC1") (pin "AB17") (pinfunction "IO_310_AB17") (pintype "bidirectional"))
    )
    (net (code "332") (name "IO311") (class "Default")
      (node (ref "IC1") (pin "AB18") (pinfunction "IO_311_AB18") (pintype "bidirectional"))
    )
    (net (code "333") (name "IO312") (class "Default")
      (node (ref "IC1") (pin "AB19") (pinfunction "IO_312_AB19") (pintype "bidirectional"))
    )
    (net (code "334") (name "IO313") (class "Default")
      (node (ref "IC1") (pin "AB20") (pinfunction "IO_313_AB20") (pintype "bidirectional"))
    )
    (net (code "335") (name "MSEL0") (class "Default")
      (node (ref "IC1") (pin "M17") (pinfunction "MSEL0_M17") (pintype "bidirectional"))
      (node (ref "R6") (pin "P$1") (pinfunction "P$1_P$1") (pintype "bidirectional"))
    )
    (net (code "336") (name "MSEL1") (class "Default")
      (node (ref "IC1") (pin "L18") (pinfunction "MSEL1_L18") (pintype "bidirectional"))
      (node (ref "R7") (pin "P$1") (pinfunction "P$1_P$1") (pintype "bidirectional"))
    )
    (net (code "337") (name "MSEL2") (class "Default")
      (node (ref "IC1") (pin "L17") (pinfunction "MSEL2_L17") (pintype "bidirectional"))
      (node (ref "R8") (pin "P$1") (pinfunction "P$1_P$1") (pintype "bidirectional"))
    )
    (net (code "338") (name "MSEL3") (class "Default")
      (node (ref "IC1") (pin "K20") (pinfunction "MSEL3_K20") (pintype "bidirectional"))
      (node (ref "R9") (pin "P$1") (pinfunction "P$1_P$1") (pintype "bidirectional"))
    )
    (net (code "339") (name "NCE") (class "Default")
      (node (ref "IC1") (pin "L3") (pinfunction "NCE_L3") (pintype "bidirectional"))
      (node (ref "R4") (pin "P$1") (pinfunction "P$1_P$1") (pintype "bidirectional"))
    )
    (net (code "340") (name "NCONFIG") (class "Default")
      (node (ref "IC1") (pin "K5") (pinfunction "NCONFIG_K5") (pintype "bidirectional"))
      (node (ref "R2") (pin "P$1") (pinfunction "P$1_P$1") (pintype "bidirectional"))
      (node (ref "SW1") (pin "2") (pinfunction "A1_2") (pintype "bidirectional"))
    )
    (net (code "341") (name "NCSO") (class "Default")
      (node (ref "IC1") (pin "E2") (pinfunction "IO_65_E2") (pintype "bidirectional"))
      (node (ref "IC2") (pin "1") (pinfunction "NCS_1") (pintype "bidirectional"))
    )
    (net (code "342") (name "NSTATUS") (class "Default")
      (node (ref "IC1") (pin "K6") (pinfunction "NSTATUS_K6") (pintype "bidirectional"))
      (node (ref "R5") (pin "P$1") (pinfunction "P$1_P$1") (pintype "bidirectional"))
    )
    (net (code "343") (name "Net-(LED33-PadA)") (class "Default")
      (node (ref "LED33") (pin "A") (pinfunction "A_A") (pintype "passive"))
      (node (ref "R45") (pin "P$2") (pinfunction "P$2_P$2") (pintype "bidirectional"))
    )
    (net (code "344") (name "Net-(LED34-PadA)") (class "Default")
      (node (ref "LED34") (pin "A") (pinfunction "A_A") (pintype "passive"))
      (node (ref "R44") (pin "P$2") (pinfunction "P$2_P$2") (pintype "bidirectional"))
    )
    (net (code "345") (name "Net-(LED35-PadA)") (class "Default")
      (node (ref "LED35") (pin "A") (pinfunction "A_A") (pintype "passive"))
      (node (ref "R43") (pin "P$2") (pinfunction "P$2_P$2") (pintype "bidirectional"))
    )
    (net (code "346") (name "Net-(LED36-PadA)") (class "Default")
      (node (ref "LED36") (pin "A") (pinfunction "A_A") (pintype "passive"))
      (node (ref "R42") (pin "P$2") (pinfunction "P$2_P$2") (pintype "bidirectional"))
    )
    (net (code "347") (name "Net-(LED37-PadA)") (class "Default")
      (node (ref "LED37") (pin "A") (pinfunction "A_A") (pintype "passive"))
      (node (ref "R41") (pin "P$2") (pinfunction "P$2_P$2") (pintype "bidirectional"))
    )
    (net (code "348") (name "Net-(LED38-PadA)") (class "Default")
      (node (ref "LED38") (pin "A") (pinfunction "A_A") (pintype "passive"))
      (node (ref "R40") (pin "P$2") (pinfunction "P$2_P$2") (pintype "bidirectional"))
    )
    (net (code "349") (name "Net-(LED39-PadA)") (class "Default")
      (node (ref "LED39") (pin "A") (pinfunction "A_A") (pintype "passive"))
      (node (ref "R39") (pin "P$2") (pinfunction "P$2_P$2") (pintype "bidirectional"))
    )
    (net (code "350") (name "Net-(LED40-PadA)") (class "Default")
      (node (ref "LED40") (pin "A") (pinfunction "A_A") (pintype "passive"))
      (node (ref "R38") (pin "P$2") (pinfunction "P$2_P$2") (pintype "bidirectional"))
    )
    (net (code "351") (name "TCK") (class "Default")
      (node (ref "IC1") (pin "L2") (pinfunction "TCK_L2") (pintype "bidirectional"))
      (node (ref "J1") (pin "1") (pinfunction "1_1") (pintype "passive"))
    )
    (net (code "352") (name "TDI") (class "Default")
      (node (ref "IC1") (pin "L5") (pinfunction "TDI_L5") (pintype "bidirectional"))
      (node (ref "J1") (pin "9") (pinfunction "9_9") (pintype "passive"))
    )
    (net (code "353") (name "TDO") (class "Default")
      (node (ref "IC1") (pin "L4") (pinfunction "TDO_L4") (pintype "bidirectional"))
      (node (ref "J1") (pin "3") (pinfunction "3_3") (pintype "passive"))
    )
    (net (code "354") (name "TMS") (class "Default")
      (node (ref "IC1") (pin "L1") (pinfunction "TMS_L1") (pintype "bidirectional"))
      (node (ref "J1") (pin "5") (pinfunction "5_5") (pintype "passive"))
    )
    (net (code "355") (name "VCCA") (class "Default")
      (node (ref "C26") (pin "2") (pinfunction "2_2") (pintype "passive"))
      (node (ref "IC1") (pin "F18") (pinfunction "VCCA2_F18") (pintype "bidirectional"))
      (node (ref "IC1") (pin "G6") (pinfunction "VCCA3_G6") (pintype "bidirectional"))
      (node (ref "IC1") (pin "T6") (pinfunction "VCCA1_T6") (pintype "bidirectional"))
      (node (ref "IC1") (pin "U18") (pinfunction "VCCA4_U18") (pintype "bidirectional"))
      (node (ref "R20") (pin "P$2") (pinfunction "P$2_P$2") (pintype "bidirectional"))
    )
    (net (code "356") (name "VCCINT") (class "Default")
      (node (ref "C24") (pin "2") (pinfunction "2_2") (pintype "passive"))
      (node (ref "IC1") (pin "G12") (pinfunction "VCCINT_1_G12") (pintype "bidirectional"))
      (node (ref "IC1") (pin "H9") (pinfunction "VCCINT_2_H9") (pintype "bidirectional"))
      (node (ref "IC1") (pin "J10") (pinfunction "VCCINT_3_J10") (pintype "bidirectional"))
      (node (ref "IC1") (pin "J11") (pinfunction "VCCINT_4_J11") (pintype "bidirectional"))
      (node (ref "IC1") (pin "J12") (pinfunction "VCCINT_5_J12") (pintype "bidirectional"))
      (node (ref "IC1") (pin "J13") (pinfunction "VCCINT_6_J13") (pintype "bidirectional"))
      (node (ref "IC1") (pin "J14") (pinfunction "VCCINT_7_J14") (pintype "bidirectional"))
      (node (ref "IC1") (pin "J16") (pinfunction "VCCINT_8_J16") (pintype "bidirectional"))
      (node (ref "IC1") (pin "K14") (pinfunction "VCCINT_10_K14") (pintype "bidirectional"))
      (node (ref "IC1") (pin "K15") (pinfunction "VCCINT_11_K15") (pintype "bidirectional"))
      (node (ref "IC1") (pin "K9") (pinfunction "VCCINT_9_K9") (pintype "bidirectional"))
      (node (ref "IC1") (pin "L14") (pinfunction "VCCINT_13_L14") (pintype "bidirectional"))
      (node (ref "IC1") (pin "L16") (pinfunction "VCCINT_14_L16") (pintype "bidirectional"))
      (node (ref "IC1") (pin "L9") (pinfunction "VCCINT_12_L9") (pintype "bidirectional"))
      (node (ref "IC1") (pin "M14") (pinfunction "VCCINT_16_M14") (pintype "bidirectional"))
      (node (ref "IC1") (pin "M15") (pinfunction "VCCINT_17_M15") (pintype "bidirectional"))
      (node (ref "IC1") (pin "M9") (pinfunction "VCCINT_15_M9") (pintype "bidirectional"))
      (node (ref "IC1") (pin "N14") (pinfunction "VCCINT_19_N14") (pintype "bidirectional"))
      (node (ref "IC1") (pin "N9") (pinfunction "VCCINT_18_N9") (pintype "bidirectional"))
      (node (ref "IC1") (pin "P10") (pinfunction "VCCINT_21_P10") (pintype "bidirectional"))
      (node (ref "IC1") (pin "P11") (pinfunction "VCCINT_22_P11") (pintype "bidirectional"))
      (node (ref "IC1") (pin "P12") (pinfunction "VCCINT_23_P12") (pintype "bidirectional"))
      (node (ref "IC1") (pin "P13") (pinfunction "VCCINT_24_P13") (pintype "bidirectional"))
      (node (ref "IC1") (pin "P14") (pinfunction "VCCINT_25_P14") (pintype "bidirectional"))
      (node (ref "IC1") (pin "P9") (pinfunction "VCCINT_20_P9") (pintype "bidirectional"))
      (node (ref "IC1") (pin "R10") (pinfunction "VCCINT_27_R10") (pintype "bidirectional"))
      (node (ref "IC1") (pin "R12") (pinfunction "VCCINT_28_R12") (pintype "bidirectional"))
      (node (ref "IC1") (pin "R8") (pinfunction "VCCINT_26_R8") (pintype "bidirectional"))
      (node (ref "R18") (pin "P$2") (pinfunction "P$2_P$2") (pintype "bidirectional"))
    )
    (net (code "357") (name "VCCIO") (class "Default")
      (node (ref "C16") (pin "2") (pinfunction "2_2") (pintype "passive"))
      (node (ref "C17") (pin "2") (pinfunction "2_2") (pintype "passive"))
      (node (ref "C18") (pin "2") (pinfunction "2_2") (pintype "passive"))
      (node (ref "C19") (pin "2") (pinfunction "2_2") (pintype "passive"))
      (node (ref "C20") (pin "2") (pinfunction "2_2") (pintype "passive"))
      (node (ref "C21") (pin "2") (pinfunction "2_2") (pintype "passive"))
      (node (ref "C22") (pin "2") (pinfunction "2_2") (pintype "passive"))
      (node (ref "C23") (pin "2") (pinfunction "2_2") (pintype "passive"))
      (node (ref "IC1") (pin "A2") (pinfunction "VCCIO8_1_A2") (pintype "bidirectional"))
      (node (ref "IC1") (pin "A21") (pinfunction "VCCIO7_1_A21") (pintype "bidirectional"))
      (node (ref "IC1") (pin "AA6") (pinfunction "VCCIO3_4_AA6") (pintype "bidirectional"))
      (node (ref "IC1") (pin "AB2") (pinfunction "VCCIO3_5_AB2") (pintype "bidirectional"))
      (node (ref "IC1") (pin "AB21") (pinfunction "VCCIO4_5_AB21") (pintype "bidirectional"))
      (node (ref "IC1") (pin "D11") (pinfunction "VCCIO8_4_D11") (pintype "bidirectional"))
      (node (ref "IC1") (pin "D12") (pinfunction "VCCIO7_2_D12") (pintype "bidirectional"))
      (node (ref "IC1") (pin "D14") (pinfunction "VCCIO7_3_D14") (pintype "bidirectional"))
      (node (ref "IC1") (pin "D16") (pinfunction "VCCIO7_4_D16") (pintype "bidirectional"))
      (node (ref "IC1") (pin "D18") (pinfunction "VCCIO7_5_D18") (pintype "bidirectional"))
      (node (ref "IC1") (pin "D4") (pinfunction "VCCIO1_1_D4") (pintype "bidirectional"))
      (node (ref "IC1") (pin "D5") (pinfunction "VCCIO8_2_D5") (pintype "bidirectional"))
      (node (ref "IC1") (pin "D9") (pinfunction "VCCIO8_3_D9") (pintype "bidirectional"))
      (node (ref "IC1") (pin "E19") (pinfunction "VCCIO6_1_E19") (pintype "bidirectional"))
      (node (ref "IC1") (pin "E8") (pinfunction "VCCIO8_5_E8") (pintype "bidirectional"))
      (node (ref "IC1") (pin "F4") (pinfunction "VCCIO1_2_F4") (pintype "bidirectional"))
      (node (ref "IC1") (pin "G19") (pinfunction "VCCIO6_2_G19") (pintype "bidirectional"))
      (node (ref "IC1") (pin "H4") (pinfunction "VCCIO1_3_H4") (pintype "bidirectional"))
      (node (ref "IC1") (pin "J20") (pinfunction "VCCIO6_3_J20") (pintype "bidirectional"))
      (node (ref "IC1") (pin "K4") (pinfunction "VCCIO1_4_K4") (pintype "bidirectional"))
      (node (ref "IC1") (pin "L19") (pinfunction "VCCIO6_4_L19") (pintype "bidirectional"))
      (node (ref "IC1") (pin "N4") (pinfunction "VCCIO2_1_N4") (pintype "bidirectional"))
      (node (ref "IC1") (pin "P18") (pinfunction "VCCIO5_1_P18") (pintype "bidirectional"))
      (node (ref "IC1") (pin "R4") (pinfunction "VCCIO2_2_R4") (pintype "bidirectional"))
      (node (ref "IC1") (pin "T19") (pinfunction "VCCIO5_2_T19") (pintype "bidirectional"))
      (node (ref "IC1") (pin "U4") (pinfunction "VCCIO2_3_U4") (pintype "bidirectional"))
      (node (ref "IC1") (pin "V19") (pinfunction "VCCIO5_3_V19") (pintype "bidirectional"))
      (node (ref "IC1") (pin "W11") (pinfunction "VCCIO3_3_W11") (pintype "bidirectional"))
      (node (ref "IC1") (pin "W12") (pinfunction "VCCIO4_1_W12") (pintype "bidirectional"))
      (node (ref "IC1") (pin "W16") (pinfunction "VCCIO4_2_W16") (pintype "bidirectional"))
      (node (ref "IC1") (pin "W18") (pinfunction "VCCIO4_3_W18") (pintype "bidirectional"))
      (node (ref "IC1") (pin "W4") (pinfunction "VCCIO2_4_W4") (pintype "bidirectional"))
      (node (ref "IC1") (pin "W5") (pinfunction "VCCIO3_1_W5") (pintype "bidirectional"))
      (node (ref "IC1") (pin "W9") (pinfunction "VCCIO3_2_W9") (pintype "bidirectional"))
      (node (ref "IC1") (pin "Y14") (pinfunction "VCCIO4_4_Y14") (pintype "bidirectional"))
      (node (ref "IC1") (pin "Y19") (pinfunction "VCCIO5_4_Y19") (pintype "bidirectional"))
      (node (ref "R17") (pin "P$2") (pinfunction "P$2_P$2") (pintype "bidirectional"))
    )
    (net (code "358") (name "VCCPLL") (class "Default")
      (node (ref "C25") (pin "2") (pinfunction "2_2") (pintype "passive"))
      (node (ref "IC1") (pin "E17") (pinfunction "VCCD_PLL2_E17") (pintype "bidirectional"))
      (node (ref "IC1") (pin "F6") (pinfunction "VCCD_PLL3_F6") (pintype "bidirectional"))
      (node (ref "IC1") (pin "U6") (pinfunction "VCCD_PLL1_U6") (pintype "bidirectional"))
      (node (ref "IC1") (pin "V17") (pinfunction "VCCD_PLL4_V17") (pintype "bidirectional"))
      (node (ref "R19") (pin "P$2") (pinfunction "P$2_P$2") (pintype "bidirectional"))
    )
    (net (code "359") (name "unconnected-(J1-Pad6)") (class "Default")
      (node (ref "J1") (pin "6") (pinfunction "6_6") (pintype "passive"))
    )
    (net (code "360") (name "unconnected-(J1-Pad7)") (class "Default")
      (node (ref "J1") (pin "7") (pinfunction "7_7") (pintype "passive"))
    )
    (net (code "361") (name "unconnected-(J1-Pad8)") (class "Default")
      (node (ref "J1") (pin "8") (pinfunction "8_8") (pintype "passive"))
    )
    (net (code "362") (name "unconnected-(SW1-A0-Pad1)") (class "Default")
      (node (ref "SW1") (pin "1") (pinfunction "A0_1") (pintype "bidirectional"))
    )
    (net (code "363") (name "unconnected-(SW1-B0-Pad3)") (class "Default")
      (node (ref "SW1") (pin "3") (pinfunction "B0_3") (pintype "bidirectional"))
    )
    (net (code "364") (name "unconnected-(SW2-A0-Pad1)") (class "Default")
      (node (ref "SW2") (pin "1") (pinfunction "A0_1") (pintype "bidirectional"))
    )
    (net (code "365") (name "unconnected-(SW2-B0-Pad3)") (class "Default")
      (node (ref "SW2") (pin "3") (pinfunction "B0_3") (pintype "bidirectional"))
    )
    (net (code "366") (name "unconnected-(Y1-EN-Pad1)") (class "Default")
      (node (ref "Y1") (pin "1") (pinfunction "EN_1") (pintype "bidirectional"))
    )
  )
)
